# Cross.net
KiCad netlist of a schematic drawn in Altium Designer
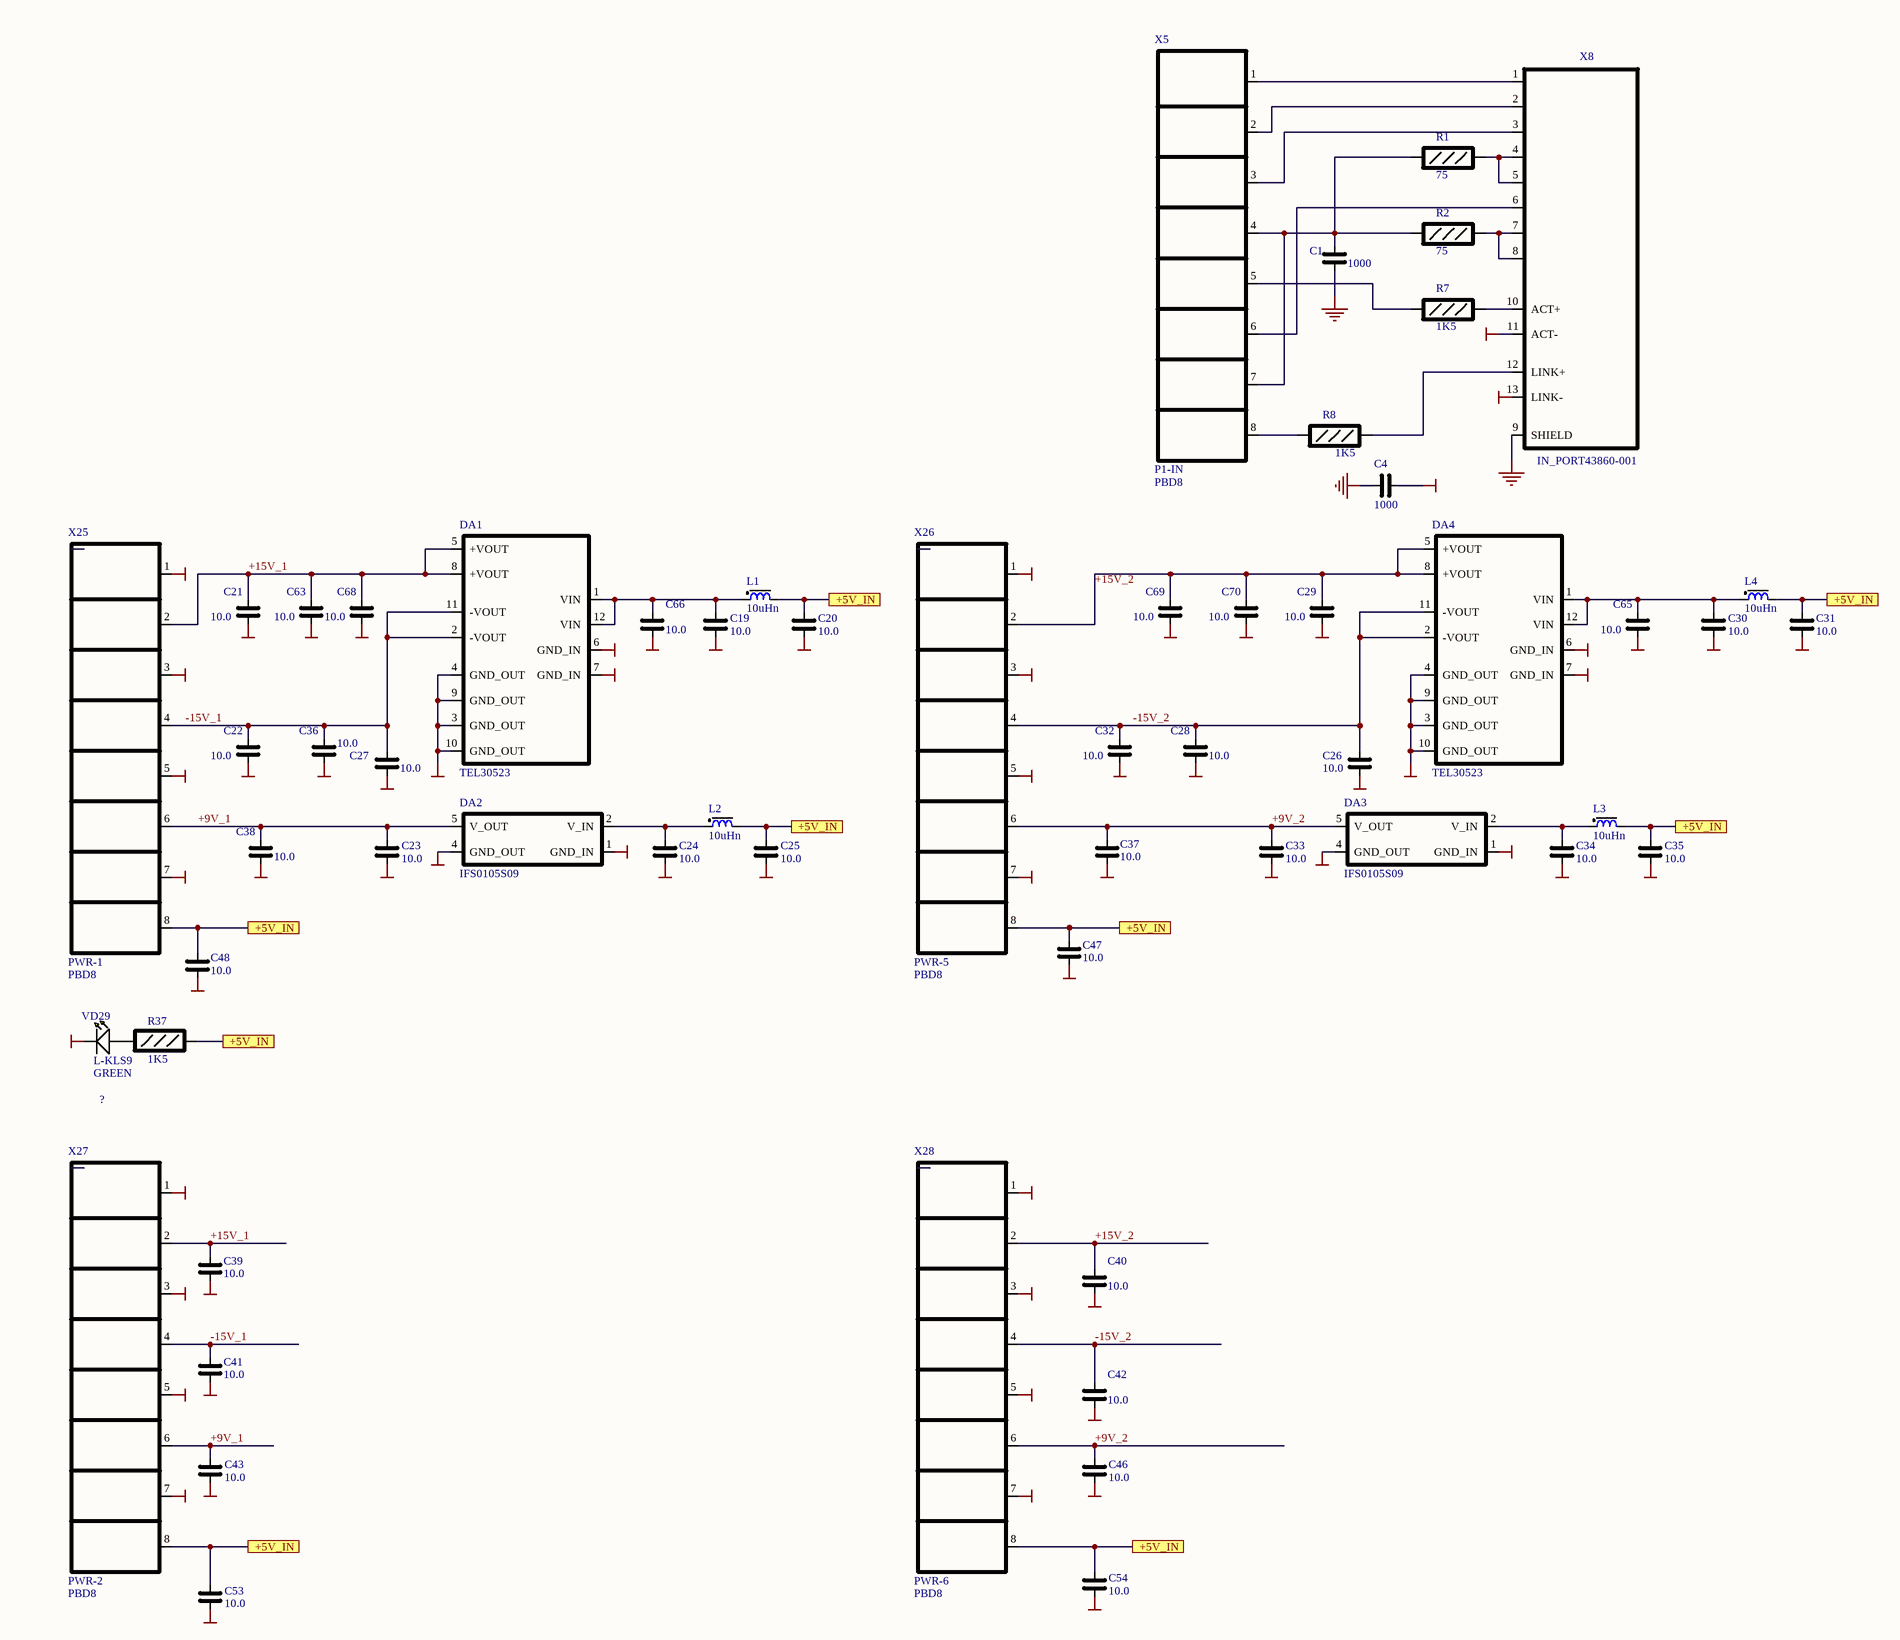
[diagram p0: Cross.SchDoc, top left]
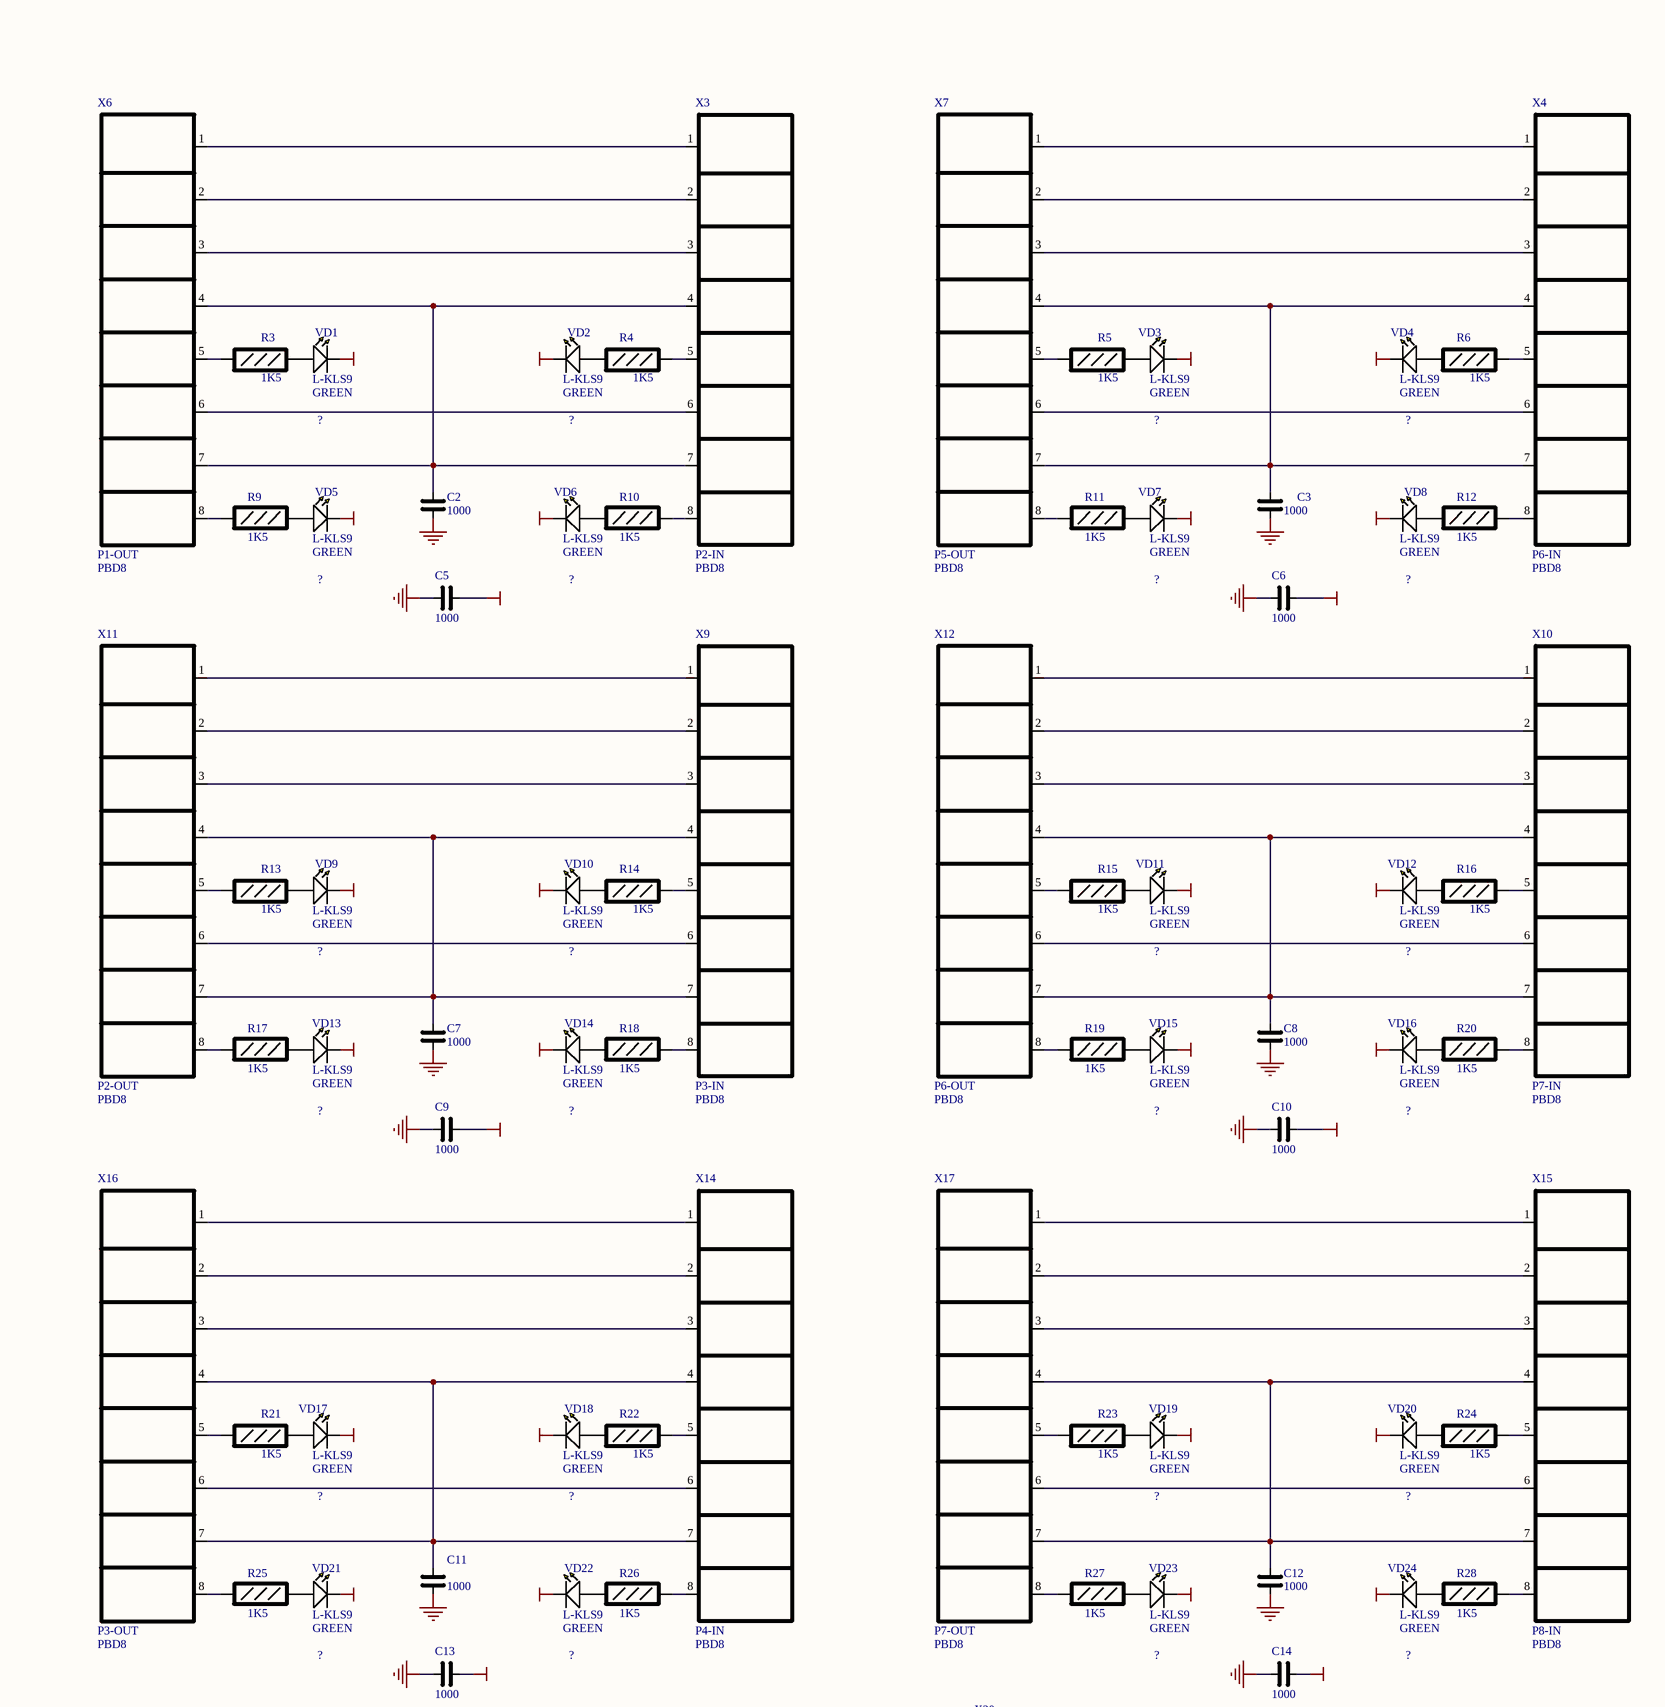
[diagram p1: Cross.SchDoc, top right]
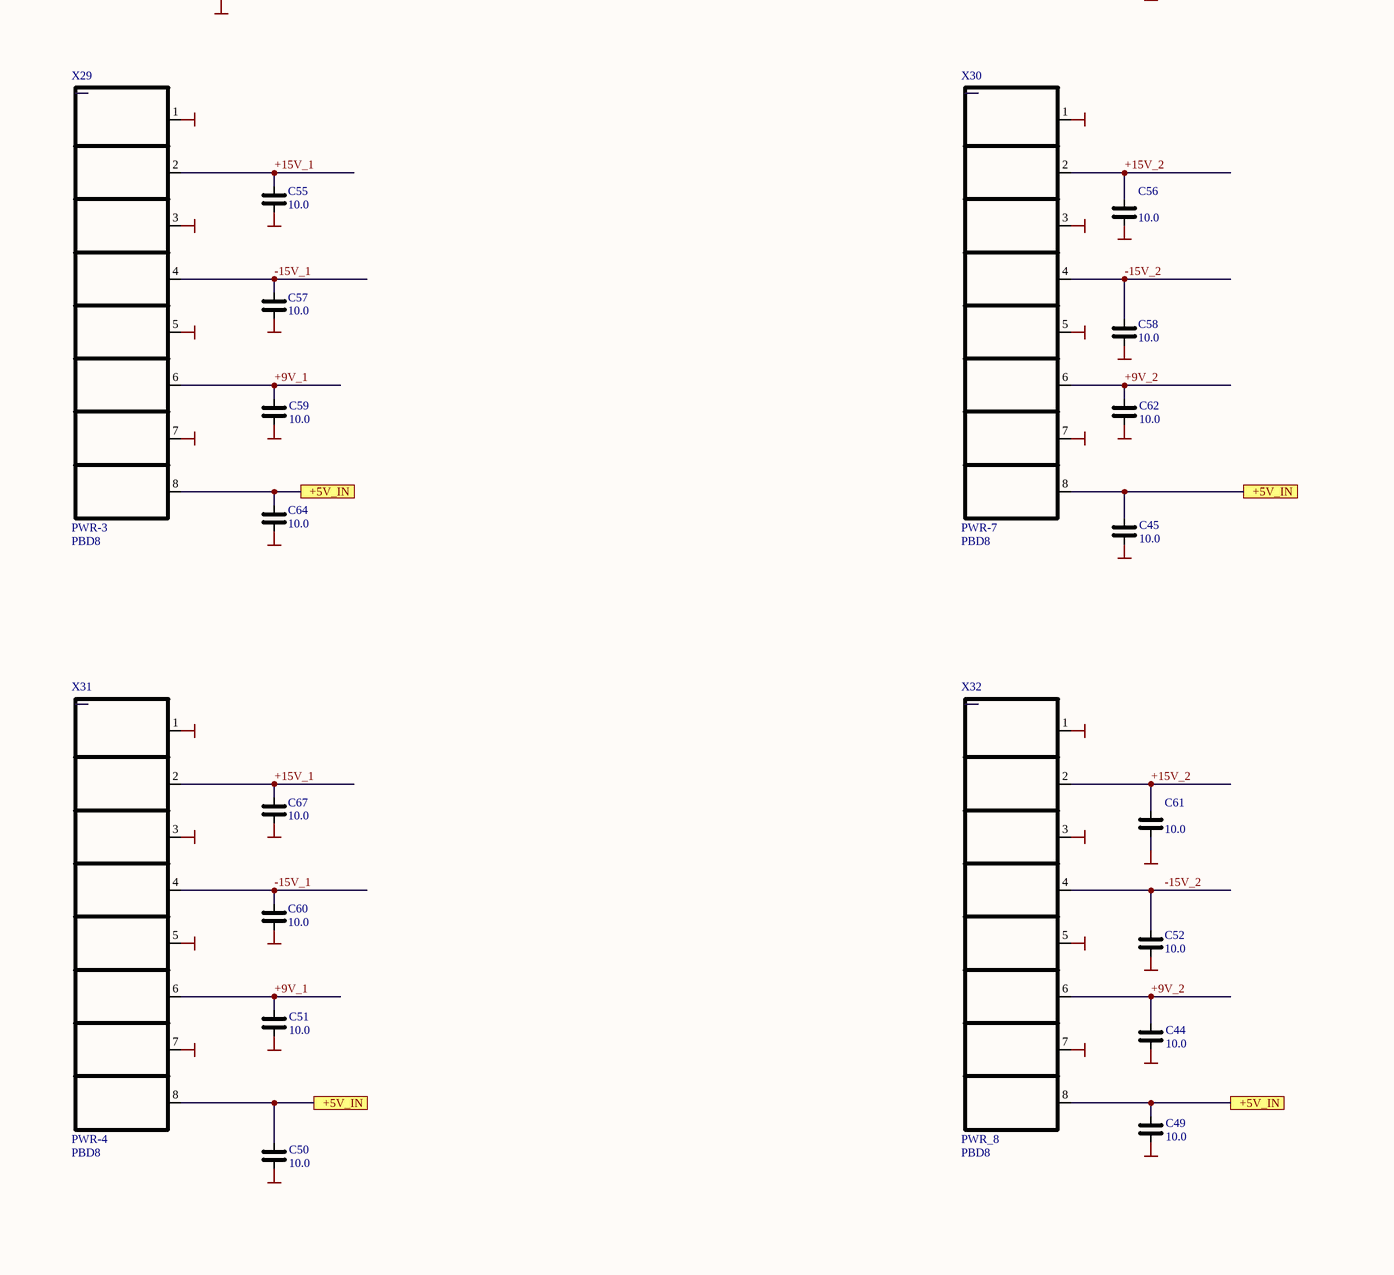
[diagram p2: Cross.SchDoc, bottom left]
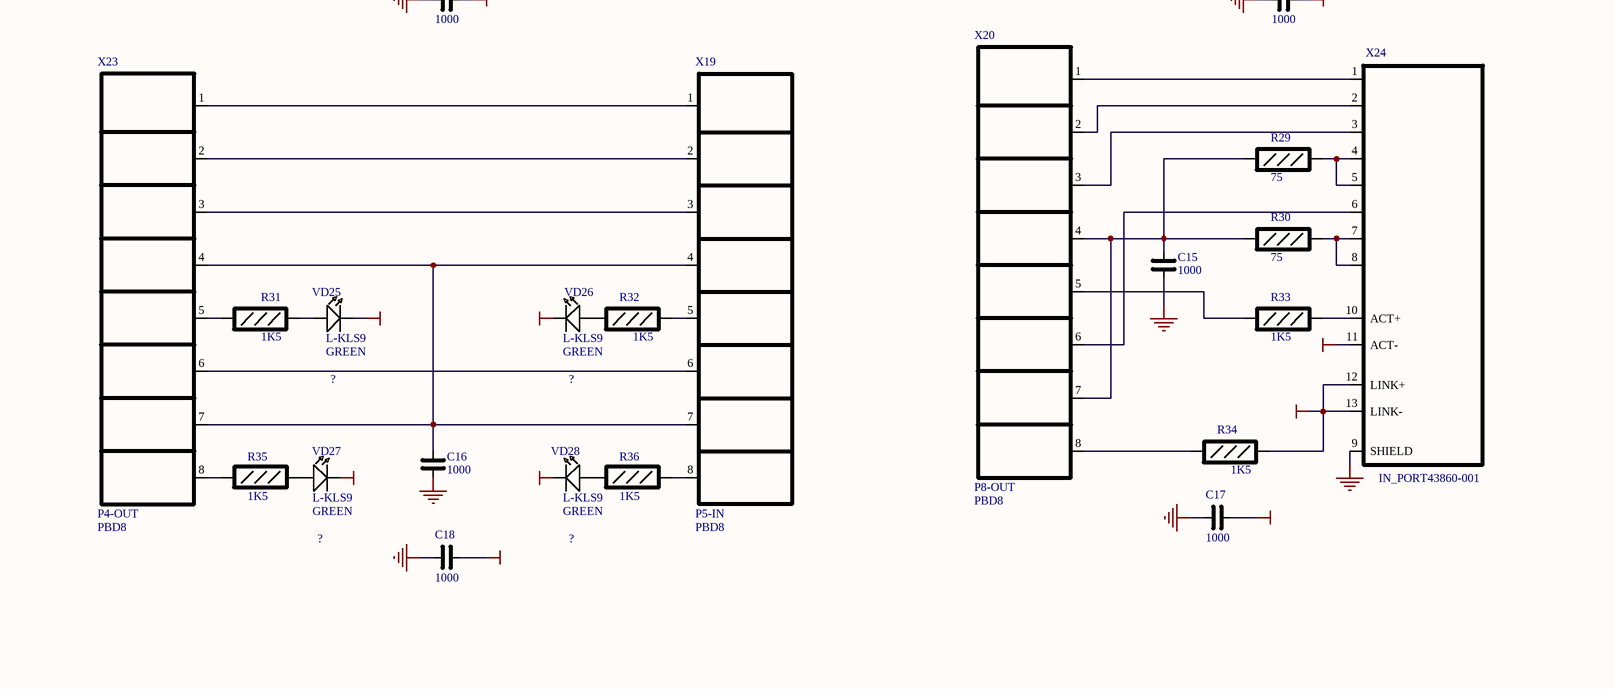
[diagram p3: Cross.SchDoc, bottom right]

(export (version "E")
  (design (tool "Eeschema 10.0.6"))
  (components
    (comp (ref "C1")
      (value "1000")
      (footprint "CAPC3225X168N")
      (description "Chip capasitor 1210")
      (libsource (lib "L1") (part "CAP1210"))
    )
    (comp (ref "C2")
      (value "1000")
      (footprint "CAPC3225X168N")
      (description "Chip capasitor 1210")
      (libsource (lib "L1") (part "CAP1210"))
    )
    (comp (ref "C3")
      (value "1000")
      (footprint "CAPC3225X168N")
      (description "Chip capasitor 1210")
      (libsource (lib "L1") (part "CAP1210"))
    )
    (comp (ref "C4")
      (value "1000")
      (footprint "CAPC3225X168N")
      (description "Chip capasitor 1210")
      (libsource (lib "L1") (part "CAP1210"))
    )
    (comp (ref "C5")
      (value "1000")
      (footprint "CAPC3225X168N")
      (description "Chip capasitor 1210")
      (libsource (lib "L1") (part "CAP1210"))
    )
    (comp (ref "C6")
      (value "1000")
      (footprint "CAPC3225X168N")
      (description "Chip capasitor 1210")
      (libsource (lib "L1") (part "CAP1210"))
    )
    (comp (ref "C7")
      (value "1000")
      (footprint "CAPC3225X168N")
      (description "Chip capasitor 1210")
      (libsource (lib "L1") (part "CAP1210"))
    )
    (comp (ref "C8")
      (value "1000")
      (footprint "CAPC3225X168N")
      (description "Chip capasitor 1210")
      (libsource (lib "L1") (part "CAP1210"))
    )
    (comp (ref "C9")
      (value "1000")
      (footprint "CAPC3225X168N")
      (description "Chip capasitor 1210")
      (libsource (lib "L1") (part "CAP1210"))
    )
    (comp (ref "C10")
      (value "1000")
      (footprint "CAPC3225X168N")
      (description "Chip capasitor 1210")
      (libsource (lib "L1") (part "CAP1210"))
    )
    (comp (ref "C11")
      (value "1000")
      (footprint "CAPC3225X168N")
      (description "Chip capasitor 1210")
      (libsource (lib "L1") (part "CAP1210"))
    )
    (comp (ref "C12")
      (value "1000")
      (footprint "CAPC3225X168N")
      (description "Chip capasitor 1210")
      (libsource (lib "L1") (part "CAP1210"))
    )
    (comp (ref "C13")
      (value "1000")
      (footprint "CAPC3225X168N")
      (description "Chip capasitor 1210")
      (libsource (lib "L1") (part "CAP1210"))
    )
    (comp (ref "C14")
      (value "1000")
      (footprint "CAPC3225X168N")
      (description "Chip capasitor 1210")
      (libsource (lib "L1") (part "CAP1210"))
    )
    (comp (ref "C15")
      (value "1000")
      (footprint "CAPC3225X168N")
      (description "Chip capasitor 1210")
      (libsource (lib "L1") (part "CAP1210"))
    )
    (comp (ref "C16")
      (value "1000")
      (footprint "CAPC3225X168N")
      (description "Chip capasitor 1210")
      (libsource (lib "L1") (part "CAP1210"))
    )
    (comp (ref "C17")
      (value "1000")
      (footprint "CAPC3225X168N")
      (description "Chip capasitor 1210")
      (libsource (lib "L1") (part "CAP1210"))
    )
    (comp (ref "C18")
      (value "1000")
      (footprint "CAPC3225X168N")
      (description "Chip capasitor 1210")
      (libsource (lib "L1") (part "CAP1210"))
    )
    (comp (ref "C19")
      (value "10.0")
      (footprint "CAPC2012X135N")
      (description "Chip capasitor 0805")
      (libsource (lib "L1") (part "CAP0805"))
    )
    (comp (ref "C20")
      (value "10.0")
      (footprint "CAPC2012X135N")
      (description "Chip capasitor 0805")
      (libsource (lib "L1") (part "CAP0805"))
    )
    (comp (ref "C21")
      (value "10.0")
      (footprint "CAPC2012X135N")
      (description "Chip capasitor 0805")
      (libsource (lib "L1") (part "CAP0805"))
    )
    (comp (ref "C22")
      (value "10.0")
      (footprint "CAPC2012X135N")
      (description "Chip capasitor 0805")
      (libsource (lib "L1") (part "CAP0805"))
    )
    (comp (ref "C23")
      (value "10.0")
      (footprint "CAPC2012X135N")
      (description "Chip capasitor 0805")
      (libsource (lib "L1") (part "CAP0805"))
    )
    (comp (ref "C24")
      (value "10.0")
      (footprint "CAPC2012X135N")
      (description "Chip capasitor 0805")
      (libsource (lib "L1") (part "CAP0805"))
    )
    (comp (ref "C25")
      (value "10.0")
      (footprint "CAPC2012X135N")
      (description "Chip capasitor 0805")
      (libsource (lib "L1") (part "CAP0805"))
    )
    (comp (ref "C26")
      (value "10.0")
      (footprint "CAPC2012X135N")
      (description "Chip capasitor 0805")
      (libsource (lib "L1") (part "CAP0805"))
    )
    (comp (ref "C27")
      (value "10.0")
      (footprint "CAPC2012X135N")
      (description "Chip capasitor 0805")
      (libsource (lib "L1") (part "CAP0805"))
    )
    (comp (ref "C28")
      (value "10.0")
      (footprint "CAPC2012X135N")
      (description "Chip capasitor 0805")
      (libsource (lib "L1") (part "CAP0805"))
    )
    (comp (ref "C29")
      (value "10.0")
      (footprint "CAPC2012X135N")
      (description "Chip capasitor 0805")
      (libsource (lib "L1") (part "CAP0805"))
    )
    (comp (ref "C30")
      (value "10.0")
      (footprint "CAPC2012X135N")
      (description "Chip capasitor 0805")
      (libsource (lib "L1") (part "CAP0805"))
    )
    (comp (ref "C31")
      (value "10.0")
      (footprint "CAPC2012X135N")
      (description "Chip capasitor 0805")
      (libsource (lib "L1") (part "CAP0805"))
    )
    (comp (ref "C32")
      (value "10.0")
      (footprint "CAPC2012X135N")
      (description "Chip capasitor 0805")
      (libsource (lib "L1") (part "CAP0805"))
    )
    (comp (ref "C33")
      (value "10.0")
      (footprint "CAPC2012X135N")
      (description "Chip capasitor 0805")
      (libsource (lib "L1") (part "CAP0805"))
    )
    (comp (ref "C34")
      (value "10.0")
      (footprint "CAPC2012X135N")
      (description "Chip capasitor 0805")
      (libsource (lib "L1") (part "CAP0805"))
    )
    (comp (ref "C35")
      (value "10.0")
      (footprint "CAPC2012X135N")
      (description "Chip capasitor 0805")
      (libsource (lib "L1") (part "CAP0805"))
    )
    (comp (ref "C36")
      (value "10.0")
      (footprint "CAPC2012X135N")
      (description "Chip capasitor 0805")
      (libsource (lib "L1") (part "CAP0805"))
    )
    (comp (ref "C37")
      (value "10.0")
      (footprint "CAPC2012X135N")
      (description "Chip capasitor 0805")
      (libsource (lib "L1") (part "CAP0805"))
    )
    (comp (ref "C38")
      (value "10.0")
      (footprint "CAPC2012X135N")
      (description "Chip capasitor 0805")
      (libsource (lib "L1") (part "CAP0805"))
    )
    (comp (ref "C39")
      (value "10.0")
      (footprint "CAPC2012X135N")
      (description "Chip capasitor 0805")
      (libsource (lib "L1") (part "CAP0805"))
    )
    (comp (ref "C40")
      (value "10.0")
      (footprint "CAPC2012X135N")
      (description "Chip capasitor 0805")
      (libsource (lib "L1") (part "CAP0805"))
    )
    (comp (ref "C41")
      (value "10.0")
      (footprint "CAPC2012X135N")
      (description "Chip capasitor 0805")
      (libsource (lib "L1") (part "CAP0805"))
    )
    (comp (ref "C42")
      (value "10.0")
      (footprint "CAPC2012X135N")
      (description "Chip capasitor 0805")
      (libsource (lib "L1") (part "CAP0805"))
    )
    (comp (ref "C43")
      (value "10.0")
      (footprint "CAPC2012X135N")
      (description "Chip capasitor 0805")
      (libsource (lib "L1") (part "CAP0805"))
    )
    (comp (ref "C44")
      (value "10.0")
      (footprint "CAPC2012X135N")
      (description "Chip capasitor 0805")
      (libsource (lib "L1") (part "CAP0805"))
    )
    (comp (ref "C45")
      (value "10.0")
      (footprint "CAPC2012X135N")
      (description "Chip capasitor 0805")
      (libsource (lib "L1") (part "CAP0805"))
    )
    (comp (ref "C46")
      (value "10.0")
      (footprint "CAPC2012X135N")
      (description "Chip capasitor 0805")
      (libsource (lib "L1") (part "CAP0805"))
    )
    (comp (ref "C47")
      (value "10.0")
      (footprint "CAPC2012X135N")
      (description "Chip capasitor 0805")
      (libsource (lib "L1") (part "CAP0805"))
    )
    (comp (ref "C48")
      (value "10.0")
      (footprint "CAPC2012X135N")
      (description "Chip capasitor 0805")
      (libsource (lib "L1") (part "CAP0805"))
    )
    (comp (ref "C49")
      (value "10.0")
      (footprint "CAPC2012X135N")
      (description "Chip capasitor 0805")
      (libsource (lib "L1") (part "CAP0805"))
    )
    (comp (ref "C50")
      (value "10.0")
      (footprint "CAPC2012X135N")
      (description "Chip capasitor 0805")
      (libsource (lib "L1") (part "CAP0805"))
    )
    (comp (ref "C51")
      (value "10.0")
      (footprint "CAPC2012X135N")
      (description "Chip capasitor 0805")
      (libsource (lib "L1") (part "CAP0805"))
    )
    (comp (ref "C52")
      (value "10.0")
      (footprint "CAPC2012X135N")
      (description "Chip capasitor 0805")
      (libsource (lib "L1") (part "CAP0805"))
    )
    (comp (ref "C53")
      (value "10.0")
      (footprint "CAPC2012X135N")
      (description "Chip capasitor 0805")
      (libsource (lib "L1") (part "CAP0805"))
    )
    (comp (ref "C54")
      (value "10.0")
      (footprint "CAPC2012X135N")
      (description "Chip capasitor 0805")
      (libsource (lib "L1") (part "CAP0805"))
    )
    (comp (ref "C55")
      (value "10.0")
      (footprint "CAPC2012X135N")
      (description "Chip capasitor 0805")
      (libsource (lib "L1") (part "CAP0805"))
    )
    (comp (ref "C56")
      (value "10.0")
      (footprint "CAPC2012X135N")
      (description "Chip capasitor 0805")
      (libsource (lib "L1") (part "CAP0805"))
    )
    (comp (ref "C57")
      (value "10.0")
      (footprint "CAPC2012X135N")
      (description "Chip capasitor 0805")
      (libsource (lib "L1") (part "CAP0805"))
    )
    (comp (ref "C58")
      (value "10.0")
      (footprint "CAPC2012X135N")
      (description "Chip capasitor 0805")
      (libsource (lib "L1") (part "CAP0805"))
    )
    (comp (ref "C59")
      (value "10.0")
      (footprint "CAPC2012X135N")
      (description "Chip capasitor 0805")
      (libsource (lib "L1") (part "CAP0805"))
    )
    (comp (ref "C60")
      (value "10.0")
      (footprint "CAPC2012X135N")
      (description "Chip capasitor 0805")
      (libsource (lib "L1") (part "CAP0805"))
    )
    (comp (ref "C61")
      (value "10.0")
      (footprint "CAPC2012X135N")
      (description "Chip capasitor 0805")
      (libsource (lib "L1") (part "CAP0805"))
    )
    (comp (ref "C62")
      (value "10.0")
      (footprint "CAPC2012X135N")
      (description "Chip capasitor 0805")
      (libsource (lib "L1") (part "CAP0805"))
    )
    (comp (ref "C63")
      (value "10.0")
      (footprint "CAPC2012X135N")
      (description "Chip capasitor 0805")
      (libsource (lib "L1") (part "CAP0805"))
    )
    (comp (ref "C64")
      (value "10.0")
      (footprint "CAPC2012X135N")
      (description "Chip capasitor 0805")
      (libsource (lib "L1") (part "CAP0805"))
    )
    (comp (ref "C65")
      (value "10.0")
      (footprint "CAPC2012X135N")
      (description "Chip capasitor 0805")
      (libsource (lib "L1") (part "CAP0805"))
    )
    (comp (ref "C66")
      (value "10.0")
      (footprint "CAPC2012X135N")
      (description "Chip capasitor 0805")
      (libsource (lib "L1") (part "CAP0805"))
    )
    (comp (ref "C67")
      (value "10.0")
      (footprint "CAPC2012X135N")
      (description "Chip capasitor 0805")
      (libsource (lib "L1") (part "CAP0805"))
    )
    (comp (ref "C68")
      (value "10.0")
      (footprint "CAPC2012X135N")
      (description "Chip capasitor 0805")
      (libsource (lib "L1") (part "CAP0805"))
    )
    (comp (ref "C69")
      (value "10.0")
      (footprint "CAPC2012X135N")
      (description "Chip capasitor 0805")
      (libsource (lib "L1") (part "CAP0805"))
    )
    (comp (ref "C70")
      (value "10.0")
      (footprint "CAPC2012X135N")
      (description "Chip capasitor 0805")
      (libsource (lib "L1") (part "CAP0805"))
    )
    (comp (ref "DA1")
      (value "TEL30523")
      (footprint "DIP_12_254_Spec0")
      (description "DC/DC convertor Vin to Dual +&- V out")
      (libsource (lib "L1") (part "TEL3-"))
    )
    (comp (ref "DA2")
      (value "IFS0105S09")
      (footprint "SOIC_8-254")
      (description "DC/DC convertor Vin4.4..5V5 to Single V out")
      (libsource (lib "L1") (part "IFS01"))
    )
    (comp (ref "DA3")
      (value "IFS0105S09")
      (footprint "SOIC_8-254")
      (description "DC/DC convertor Vin4.4..5V5 to Single V out")
      (libsource (lib "L1") (part "IFS01"))
    )
    (comp (ref "DA4")
      (value "TEL30523")
      (footprint "DIP_12_254_Spec0")
      (description "DC/DC convertor Vin to Dual +&- V out")
      (libsource (lib "L1") (part "TEL3-"))
    )
    (comp (ref "L1")
      (value "10uHn")
      (footprint "SMD2220")
      (description "Chip capasitor 1210")
      (libsource (lib "L1") (part "LQN6C"))
    )
    (comp (ref "L2")
      (value "10uHn")
      (footprint "SMD2220")
      (description "Chip capasitor 1210")
      (libsource (lib "L1") (part "LQN6C"))
    )
    (comp (ref "L3")
      (value "10uHn")
      (footprint "SMD2220")
      (description "Chip capasitor 1210")
      (libsource (lib "L1") (part "LQN6C"))
    )
    (comp (ref "L4")
      (value "10uHn")
      (footprint "SMD2220")
      (description "Chip capasitor 1210")
      (libsource (lib "L1") (part "LQN6C"))
    )
    (comp (ref "R1")
      (value "75")
      (footprint "RESC1608X50N")
      (description "Chip resistor 0603")
      (libsource (lib "L1") (part "Res0603"))
    )
    (comp (ref "R2")
      (value "75")
      (footprint "RESC1608X50N")
      (description "Chip resistor 0603")
      (libsource (lib "L1") (part "Res0603"))
    )
    (comp (ref "R3")
      (value "1K5")
      (footprint "RESC1608X50N")
      (description "Chip resistor 0603")
      (libsource (lib "L1") (part "Res0603"))
    )
    (comp (ref "R4")
      (value "1K5")
      (footprint "RESC1608X50N")
      (description "Chip resistor 0603")
      (libsource (lib "L1") (part "Res0603"))
    )
    (comp (ref "R5")
      (value "1K5")
      (footprint "RESC1608X50N")
      (description "Chip resistor 0603")
      (libsource (lib "L1") (part "Res0603"))
    )
    (comp (ref "R6")
      (value "1K5")
      (footprint "RESC1608X50N")
      (description "Chip resistor 0603")
      (libsource (lib "L1") (part "Res0603"))
    )
    (comp (ref "R7")
      (value "1K5")
      (footprint "RESC1608X50N")
      (description "Chip resistor 0603")
      (libsource (lib "L1") (part "Res0603"))
    )
    (comp (ref "R8")
      (value "1K5")
      (footprint "RESC1608X50N")
      (description "Chip resistor 0603")
      (libsource (lib "L1") (part "Res0603"))
    )
    (comp (ref "R9")
      (value "1K5")
      (footprint "RESC1608X50N")
      (description "Chip resistor 0603")
      (libsource (lib "") (part "Res0603_1"))
    )
    (comp (ref "R10")
      (value "1K5")
      (footprint "RESC1608X50N")
      (description "Chip resistor 0603")
      (libsource (lib "") (part "Res0603_1"))
    )
    (comp (ref "R11")
      (value "1K5")
      (footprint "RESC1608X50N")
      (description "Chip resistor 0603")
      (libsource (lib "") (part "Res0603_1"))
    )
    (comp (ref "R12")
      (value "1K5")
      (footprint "RESC1608X50N")
      (description "Chip resistor 0603")
      (libsource (lib "") (part "Res0603_1"))
    )
    (comp (ref "R13")
      (value "1K5")
      (footprint "RESC1608X50N")
      (description "Chip resistor 0603")
      (libsource (lib "L1") (part "Res0603"))
    )
    (comp (ref "R14")
      (value "1K5")
      (footprint "RESC1608X50N")
      (description "Chip resistor 0603")
      (libsource (lib "L1") (part "Res0603"))
    )
    (comp (ref "R15")
      (value "1K5")
      (footprint "RESC1608X50N")
      (description "Chip resistor 0603")
      (libsource (lib "L1") (part "Res0603"))
    )
    (comp (ref "R16")
      (value "1K5")
      (footprint "RESC1608X50N")
      (description "Chip resistor 0603")
      (libsource (lib "L1") (part "Res0603"))
    )
    (comp (ref "R17")
      (value "1K5")
      (footprint "RESC1608X50N")
      (description "Chip resistor 0603")
      (libsource (lib "") (part "Res0603_1"))
    )
    (comp (ref "R18")
      (value "1K5")
      (footprint "RESC1608X50N")
      (description "Chip resistor 0603")
      (libsource (lib "") (part "Res0603_1"))
    )
    (comp (ref "R19")
      (value "1K5")
      (footprint "RESC1608X50N")
      (description "Chip resistor 0603")
      (libsource (lib "") (part "Res0603_1"))
    )
    (comp (ref "R20")
      (value "1K5")
      (footprint "RESC1608X50N")
      (description "Chip resistor 0603")
      (libsource (lib "") (part "Res0603_1"))
    )
    (comp (ref "R21")
      (value "1K5")
      (footprint "RESC1608X50N")
      (description "Chip resistor 0603")
      (libsource (lib "L1") (part "Res0603"))
    )
    (comp (ref "R22")
      (value "1K5")
      (footprint "RESC1608X50N")
      (description "Chip resistor 0603")
      (libsource (lib "L1") (part "Res0603"))
    )
    (comp (ref "R23")
      (value "1K5")
      (footprint "RESC1608X50N")
      (description "Chip resistor 0603")
      (libsource (lib "L1") (part "Res0603"))
    )
    (comp (ref "R24")
      (value "1K5")
      (footprint "RESC1608X50N")
      (description "Chip resistor 0603")
      (libsource (lib "L1") (part "Res0603"))
    )
    (comp (ref "R25")
      (value "1K5")
      (footprint "RESC1608X50N")
      (description "Chip resistor 0603")
      (libsource (lib "") (part "Res0603_1"))
    )
    (comp (ref "R26")
      (value "1K5")
      (footprint "RESC1608X50N")
      (description "Chip resistor 0603")
      (libsource (lib "") (part "Res0603_1"))
    )
    (comp (ref "R27")
      (value "1K5")
      (footprint "RESC1608X50N")
      (description "Chip resistor 0603")
      (libsource (lib "") (part "Res0603_1"))
    )
    (comp (ref "R28")
      (value "1K5")
      (footprint "RESC1608X50N")
      (description "Chip resistor 0603")
      (libsource (lib "") (part "Res0603_1"))
    )
    (comp (ref "R29")
      (value "75")
      (footprint "RESC1608X50N")
      (description "Chip resistor 0603")
      (libsource (lib "L1") (part "Res0603"))
    )
    (comp (ref "R30")
      (value "75")
      (footprint "RESC1608X50N")
      (description "Chip resistor 0603")
      (libsource (lib "L1") (part "Res0603"))
    )
    (comp (ref "R31")
      (value "1K5")
      (footprint "RESC1608X50N")
      (description "Chip resistor 0603")
      (libsource (lib "L1") (part "Res0603"))
    )
    (comp (ref "R32")
      (value "1K5")
      (footprint "RESC1608X50N")
      (description "Chip resistor 0603")
      (libsource (lib "L1") (part "Res0603"))
    )
    (comp (ref "R33")
      (value "1K5")
      (footprint "RESC1608X50N")
      (description "Chip resistor 0603")
      (libsource (lib "L1") (part "Res0603"))
    )
    (comp (ref "R34")
      (value "1K5")
      (footprint "RESC1608X50N")
      (description "Chip resistor 0603")
      (libsource (lib "L1") (part "Res0603"))
    )
    (comp (ref "R35")
      (value "1K5")
      (footprint "RESC1608X50N")
      (description "Chip resistor 0603")
      (libsource (lib "") (part "Res0603_1"))
    )
    (comp (ref "R36")
      (value "1K5")
      (footprint "RESC1608X50N")
      (description "Chip resistor 0603")
      (libsource (lib "") (part "Res0603_1"))
    )
    (comp (ref "R37")
      (value "1K5")
      (footprint "RESC1608X50N")
      (description "Chip resistor 0603")
      (libsource (lib "") (part "Res0603_1"))
    )
    (comp (ref "VD1")
      (value "?")
      (footprint "LED0603")
      (description "Chip LED SMD 0603")
      (fields (field (name "DEVICE") "L-KLS9") (field (name "COLOR") "GREEN"))
      (libsource (lib "L1") (part "L-KLS9-T0603"))
    )
    (comp (ref "VD2")
      (value "?")
      (footprint "LED0603")
      (description "Chip LED SMD 0603")
      (fields (field (name "DEVICE") "L-KLS9") (field (name "COLOR") "GREEN"))
      (libsource (lib "L1") (part "L-KLS9-T0603"))
    )
    (comp (ref "VD3")
      (value "?")
      (footprint "LED0603")
      (description "Chip LED SMD 0603")
      (fields (field (name "DEVICE") "L-KLS9") (field (name "COLOR") "GREEN"))
      (libsource (lib "L1") (part "L-KLS9-T0603"))
    )
    (comp (ref "VD4")
      (value "?")
      (footprint "LED0603")
      (description "Chip LED SMD 0603")
      (fields (field (name "DEVICE") "L-KLS9") (field (name "COLOR") "GREEN"))
      (libsource (lib "L1") (part "L-KLS9-T0603"))
    )
    (comp (ref "VD5")
      (value "?")
      (footprint "LED0603")
      (description "Chip LED SMD 0603")
      (fields (field (name "DEVICE") "L-KLS9") (field (name "COLOR") "GREEN"))
      (libsource (lib "L1") (part "L-KLS9-T0603"))
    )
    (comp (ref "VD6")
      (value "?")
      (footprint "LED0603")
      (description "Chip LED SMD 0603")
      (fields (field (name "DEVICE") "L-KLS9") (field (name "COLOR") "GREEN"))
      (libsource (lib "L1") (part "L-KLS9-T0603"))
    )
    (comp (ref "VD7")
      (value "?")
      (footprint "LED0603")
      (description "Chip LED SMD 0603")
      (fields (field (name "DEVICE") "L-KLS9") (field (name "COLOR") "GREEN"))
      (libsource (lib "L1") (part "L-KLS9-T0603"))
    )
    (comp (ref "VD8")
      (value "?")
      (footprint "LED0603")
      (description "Chip LED SMD 0603")
      (fields (field (name "DEVICE") "L-KLS9") (field (name "COLOR") "GREEN"))
      (libsource (lib "L1") (part "L-KLS9-T0603"))
    )
    (comp (ref "VD9")
      (value "?")
      (footprint "LED0603")
      (description "Chip LED SMD 0603")
      (fields (field (name "DEVICE") "L-KLS9") (field (name "COLOR") "GREEN"))
      (libsource (lib "L1") (part "L-KLS9-T0603"))
    )
    (comp (ref "VD10")
      (value "?")
      (footprint "LED0603")
      (description "Chip LED SMD 0603")
      (fields (field (name "DEVICE") "L-KLS9") (field (name "COLOR") "GREEN"))
      (libsource (lib "L1") (part "L-KLS9-T0603"))
    )
    (comp (ref "VD11")
      (value "?")
      (footprint "LED0603")
      (description "Chip LED SMD 0603")
      (fields (field (name "DEVICE") "L-KLS9") (field (name "COLOR") "GREEN"))
      (libsource (lib "L1") (part "L-KLS9-T0603"))
    )
    (comp (ref "VD12")
      (value "?")
      (footprint "LED0603")
      (description "Chip LED SMD 0603")
      (fields (field (name "DEVICE") "L-KLS9") (field (name "COLOR") "GREEN"))
      (libsource (lib "L1") (part "L-KLS9-T0603"))
    )
    (comp (ref "VD13")
      (value "?")
      (footprint "LED0603")
      (description "Chip LED SMD 0603")
      (fields (field (name "DEVICE") "L-KLS9") (field (name "COLOR") "GREEN"))
      (libsource (lib "L1") (part "L-KLS9-T0603"))
    )
    (comp (ref "VD14")
      (value "?")
      (footprint "LED0603")
      (description "Chip LED SMD 0603")
      (fields (field (name "DEVICE") "L-KLS9") (field (name "COLOR") "GREEN"))
      (libsource (lib "L1") (part "L-KLS9-T0603"))
    )
    (comp (ref "VD15")
      (value "?")
      (footprint "LED0603")
      (description "Chip LED SMD 0603")
      (fields (field (name "DEVICE") "L-KLS9") (field (name "COLOR") "GREEN"))
      (libsource (lib "L1") (part "L-KLS9-T0603"))
    )
    (comp (ref "VD16")
      (value "?")
      (footprint "LED0603")
      (description "Chip LED SMD 0603")
      (fields (field (name "DEVICE") "L-KLS9") (field (name "COLOR") "GREEN"))
      (libsource (lib "L1") (part "L-KLS9-T0603"))
    )
    (comp (ref "VD17")
      (value "?")
      (footprint "LED0603")
      (description "Chip LED SMD 0603")
      (fields (field (name "DEVICE") "L-KLS9") (field (name "COLOR") "GREEN"))
      (libsource (lib "L1") (part "L-KLS9-T0603"))
    )
    (comp (ref "VD18")
      (value "?")
      (footprint "LED0603")
      (description "Chip LED SMD 0603")
      (fields (field (name "DEVICE") "L-KLS9") (field (name "COLOR") "GREEN"))
      (libsource (lib "L1") (part "L-KLS9-T0603"))
    )
    (comp (ref "VD19")
      (value "?")
      (footprint "LED0603")
      (description "Chip LED SMD 0603")
      (fields (field (name "DEVICE") "L-KLS9") (field (name "COLOR") "GREEN"))
      (libsource (lib "L1") (part "L-KLS9-T0603"))
    )
    (comp (ref "VD20")
      (value "?")
      (footprint "LED0603")
      (description "Chip LED SMD 0603")
      (fields (field (name "DEVICE") "L-KLS9") (field (name "COLOR") "GREEN"))
      (libsource (lib "L1") (part "L-KLS9-T0603"))
    )
    (comp (ref "VD21")
      (value "?")
      (footprint "LED0603")
      (description "Chip LED SMD 0603")
      (fields (field (name "DEVICE") "L-KLS9") (field (name "COLOR") "GREEN"))
      (libsource (lib "L1") (part "L-KLS9-T0603"))
    )
    (comp (ref "VD22")
      (value "?")
      (footprint "LED0603")
      (description "Chip LED SMD 0603")
      (fields (field (name "DEVICE") "L-KLS9") (field (name "COLOR") "GREEN"))
      (libsource (lib "L1") (part "L-KLS9-T0603"))
    )
    (comp (ref "VD23")
      (value "?")
      (footprint "LED0603")
      (description "Chip LED SMD 0603")
      (fields (field (name "DEVICE") "L-KLS9") (field (name "COLOR") "GREEN"))
      (libsource (lib "L1") (part "L-KLS9-T0603"))
    )
    (comp (ref "VD24")
      (value "?")
      (footprint "LED0603")
      (description "Chip LED SMD 0603")
      (fields (field (name "DEVICE") "L-KLS9") (field (name "COLOR") "GREEN"))
      (libsource (lib "L1") (part "L-KLS9-T0603"))
    )
    (comp (ref "VD25")
      (value "?")
      (footprint "LED0603")
      (description "Chip LED SMD 0603")
      (fields (field (name "DEVICE") "L-KLS9") (field (name "COLOR") "GREEN"))
      (libsource (lib "L1") (part "L-KLS9-T0603"))
    )
    (comp (ref "VD26")
      (value "?")
      (footprint "LED0603")
      (description "Chip LED SMD 0603")
      (fields (field (name "DEVICE") "L-KLS9") (field (name "COLOR") "GREEN"))
      (libsource (lib "L1") (part "L-KLS9-T0603"))
    )
    (comp (ref "VD27")
      (value "?")
      (footprint "LED0603")
      (description "Chip LED SMD 0603")
      (fields (field (name "DEVICE") "L-KLS9") (field (name "COLOR") "GREEN"))
      (libsource (lib "L1") (part "L-KLS9-T0603"))
    )
    (comp (ref "VD28")
      (value "?")
      (footprint "LED0603")
      (description "Chip LED SMD 0603")
      (fields (field (name "DEVICE") "L-KLS9") (field (name "COLOR") "GREEN"))
      (libsource (lib "L1") (part "L-KLS9-T0603"))
    )
    (comp (ref "VD29")
      (value "?")
      (footprint "LED0603")
      (description "Chip LED SMD 0603")
      (fields (field (name "DEVICE") "L-KLS9") (field (name "COLOR") "GREEN"))
      (libsource (lib "L1") (part "L-KLS9-T0603"))
    )
    (comp (ref "X3")
      (value "P2-IN")
      (footprint "DIP_8-254_F")
      (description "8 pin TRH socket 2.54mm pitch")
      (fields (field (name "DEVICE") "PBD8"))
      (libsource (lib "L1") (part "PBD8"))
    )
    (comp (ref "X4")
      (value "P6-IN")
      (footprint "DIP_8-254_F")
      (description "8 pin TRH socket 2.54mm pitch")
      (fields (field (name "DEVICE") "PBD8"))
      (libsource (lib "L1") (part "PBD8"))
    )
    (comp (ref "X5")
      (value "P1-IN")
      (footprint "DIP_8-254_F")
      (description "8 pin TRH socket 2.54mm pitch")
      (fields (field (name "DEVICE") "PBD8"))
      (libsource (lib "L1") (part "PBD8"))
    )
    (comp (ref "X6")
      (value "P1-OUT")
      (footprint "DIP_8-254_F")
      (description "8 pin TRH socket 2.54mm pitch")
      (fields (field (name "DEVICE") "PBD8"))
      (libsource (lib "L1") (part "PBD8"))
    )
    (comp (ref "X7")
      (value "P5-OUT")
      (footprint "DIP_8-254_F")
      (description "8 pin TRH socket 2.54mm pitch")
      (fields (field (name "DEVICE") "PBD8"))
      (libsource (lib "L1") (part "PBD8"))
    )
    (comp (ref "X8")
      (value "IN_PORT43860-001")
      (footprint "43860-0010")
      (description "RG45 THD Ethernet socket")
      (libsource (lib "L1") (part "RG45-43860-0010"))
    )
    (comp (ref "X9")
      (value "P3-IN")
      (footprint "DIP_8-254_F")
      (description "8 pin TRH socket 2.54mm pitch")
      (fields (field (name "DEVICE") "PBD8"))
      (libsource (lib "L1") (part "PBD8"))
    )
    (comp (ref "X10")
      (value "P7-IN")
      (footprint "DIP_8-254_F")
      (description "8 pin TRH socket 2.54mm pitch")
      (fields (field (name "DEVICE") "PBD8"))
      (libsource (lib "L1") (part "PBD8"))
    )
    (comp (ref "X11")
      (value "P2-OUT")
      (footprint "DIP_8-254_F")
      (description "8 pin TRH socket 2.54mm pitch")
      (fields (field (name "DEVICE") "PBD8"))
      (libsource (lib "L1") (part "PBD8"))
    )
    (comp (ref "X12")
      (value "P6-OUT")
      (footprint "DIP_8-254_F")
      (description "8 pin TRH socket 2.54mm pitch")
      (fields (field (name "DEVICE") "PBD8"))
      (libsource (lib "L1") (part "PBD8"))
    )
    (comp (ref "X14")
      (value "P4-IN")
      (footprint "DIP_8-254_F")
      (description "8 pin TRH socket 2.54mm pitch")
      (fields (field (name "DEVICE") "PBD8"))
      (libsource (lib "L1") (part "PBD8"))
    )
    (comp (ref "X15")
      (value "P8-IN")
      (footprint "DIP_8-254_F")
      (description "8 pin TRH socket 2.54mm pitch")
      (fields (field (name "DEVICE") "PBD8"))
      (libsource (lib "L1") (part "PBD8"))
    )
    (comp (ref "X16")
      (value "P3-OUT")
      (footprint "DIP_8-254_F")
      (description "8 pin TRH socket 2.54mm pitch")
      (fields (field (name "DEVICE") "PBD8"))
      (libsource (lib "L1") (part "PBD8"))
    )
    (comp (ref "X17")
      (value "P7-OUT")
      (footprint "DIP_8-254_F")
      (description "8 pin TRH socket 2.54mm pitch")
      (fields (field (name "DEVICE") "PBD8"))
      (libsource (lib "L1") (part "PBD8"))
    )
    (comp (ref "X19")
      (value "P5-IN")
      (footprint "DIP_8-254_F")
      (description "8 pin TRH socket 2.54mm pitch")
      (fields (field (name "DEVICE") "PBD8"))
      (libsource (lib "L1") (part "PBD8"))
    )
    (comp (ref "X20")
      (value "P8-OUT")
      (footprint "DIP_8-254_F")
      (description "8 pin TRH socket 2.54mm pitch")
      (fields (field (name "DEVICE") "PBD8"))
      (libsource (lib "L1") (part "PBD8"))
    )
    (comp (ref "X23")
      (value "P4-OUT")
      (footprint "DIP_8-254_F")
      (description "8 pin TRH socket 2.54mm pitch")
      (fields (field (name "DEVICE") "PBD8"))
      (libsource (lib "L1") (part "PBD8"))
    )
    (comp (ref "X24")
      (value "IN_PORT43860-001")
      (footprint "43860-0010")
      (description "RG45 THD Ethernet socket")
      (libsource (lib "L1") (part "RG45-43860-0010"))
    )
    (comp (ref "X25")
      (value "PWR-1")
      (footprint "DIP_8-254_F")
      (description "8 pin TRH socket 2.54mm pitch")
      (fields (field (name "DEVICE") "PBD8"))
      (libsource (lib "L1") (part "PBD8"))
    )
    (comp (ref "X26")
      (value "PWR-5")
      (footprint "DIP_8-254_F")
      (description "8 pin TRH socket 2.54mm pitch")
      (fields (field (name "DEVICE") "PBD8"))
      (libsource (lib "L1") (part "PBD8"))
    )
    (comp (ref "X27")
      (value "PWR-2")
      (footprint "DIP_8-254_F")
      (description "8 pin TRH socket 2.54mm pitch")
      (fields (field (name "DEVICE") "PBD8"))
      (libsource (lib "L1") (part "PBD8"))
    )
    (comp (ref "X28")
      (value "PWR-6")
      (footprint "DIP_8-254_F")
      (description "8 pin TRH socket 2.54mm pitch")
      (fields (field (name "DEVICE") "PBD8"))
      (libsource (lib "L1") (part "PBD8"))
    )
    (comp (ref "X29")
      (value "PWR-3")
      (footprint "DIP_8-254_F")
      (description "8 pin TRH socket 2.54mm pitch")
      (fields (field (name "DEVICE") "PBD8"))
      (libsource (lib "L1") (part "PBD8"))
    )
    (comp (ref "X30")
      (value "PWR-7")
      (footprint "DIP_8-254_F")
      (description "8 pin TRH socket 2.54mm pitch")
      (fields (field (name "DEVICE") "PBD8"))
      (libsource (lib "L1") (part "PBD8"))
    )
    (comp (ref "X31")
      (value "PWR-4")
      (footprint "DIP_8-254_F")
      (description "8 pin TRH socket 2.54mm pitch")
      (fields (field (name "DEVICE") "PBD8"))
      (libsource (lib "L1") (part "PBD8"))
    )
    (comp (ref "X32")
      (value "PWR_8")
      (footprint "DIP_8-254_F")
      (description "8 pin TRH socket 2.54mm pitch")
      (fields (field (name "DEVICE") "PBD8"))
      (libsource (lib "L1") (part "PBD8"))
    )
  )
  (nets
    (net (code "1") (name "/+5V_IN") (class "Default")
      (node (ref "C20") (pin "2") (pinfunction "2_2") (pintype "passive"))
      (node (ref "C25") (pin "2") (pinfunction "2_2") (pintype "passive"))
      (node (ref "C31") (pin "2") (pinfunction "2_2") (pintype "passive"))
      (node (ref "C35") (pin "2") (pinfunction "2_2") (pintype "passive"))
      (node (ref "C45") (pin "2") (pinfunction "2_2") (pintype "passive"))
      (node (ref "C47") (pin "2") (pinfunction "2_2") (pintype "passive"))
      (node (ref "C48") (pin "2") (pinfunction "2_2") (pintype "passive"))
      (node (ref "C49") (pin "2") (pinfunction "2_2") (pintype "passive"))
      (node (ref "C50") (pin "2") (pinfunction "2_2") (pintype "passive"))
      (node (ref "C53") (pin "2") (pinfunction "2_2") (pintype "passive"))
      (node (ref "C54") (pin "2") (pinfunction "2_2") (pintype "passive"))
      (node (ref "C64") (pin "2") (pinfunction "2_2") (pintype "passive"))
      (node (ref "L1") (pin "2") (pinfunction "2_2") (pintype "passive"))
      (node (ref "L2") (pin "2") (pinfunction "2_2") (pintype "passive"))
      (node (ref "L3") (pin "2") (pinfunction "2_2") (pintype "passive"))
      (node (ref "L4") (pin "2") (pinfunction "2_2") (pintype "passive"))
      (node (ref "R37") (pin "1") (pinfunction "1_1") (pintype "passive"))
      (node (ref "X25") (pin "8") (pinfunction "8_8") (pintype "passive"))
      (node (ref "X26") (pin "8") (pinfunction "8_8") (pintype "passive"))
      (node (ref "X27") (pin "8") (pinfunction "8_8") (pintype "passive"))
      (node (ref "X28") (pin "8") (pinfunction "8_8") (pintype "passive"))
      (node (ref "X29") (pin "8") (pinfunction "8_8") (pintype "passive"))
      (node (ref "X30") (pin "8") (pinfunction "8_8") (pintype "passive"))
      (node (ref "X31") (pin "8") (pinfunction "8_8") (pintype "passive"))
      (node (ref "X32") (pin "8") (pinfunction "8_8") (pintype "passive"))
    )
    (net (code "2") (name "/+9V_1") (class "Default")
      (node (ref "C23") (pin "2") (pinfunction "2_2") (pintype "passive"))
      (node (ref "C38") (pin "2") (pinfunction "2_2") (pintype "passive"))
      (node (ref "C43") (pin "2") (pinfunction "2_2") (pintype "passive"))
      (node (ref "C51") (pin "2") (pinfunction "2_2") (pintype "passive"))
      (node (ref "C59") (pin "2") (pinfunction "2_2") (pintype "passive"))
      (node (ref "DA2") (pin "5") (pinfunction "V_OUT_5") (pintype "power_in"))
      (node (ref "X25") (pin "6") (pinfunction "6_6") (pintype "passive"))
      (node (ref "X27") (pin "6") (pinfunction "6_6") (pintype "passive"))
      (node (ref "X29") (pin "6") (pinfunction "6_6") (pintype "passive"))
      (node (ref "X31") (pin "6") (pinfunction "6_6") (pintype "passive"))
    )
    (net (code "3") (name "/+9V_2") (class "Default")
      (node (ref "C33") (pin "2") (pinfunction "2_2") (pintype "passive"))
      (node (ref "C37") (pin "2") (pinfunction "2_2") (pintype "passive"))
      (node (ref "C44") (pin "2") (pinfunction "2_2") (pintype "passive"))
      (node (ref "C46") (pin "2") (pinfunction "2_2") (pintype "passive"))
      (node (ref "C62") (pin "2") (pinfunction "2_2") (pintype "passive"))
      (node (ref "DA3") (pin "5") (pinfunction "V_OUT_5") (pintype "power_in"))
      (node (ref "X26") (pin "6") (pinfunction "6_6") (pintype "passive"))
      (node (ref "X28") (pin "6") (pinfunction "6_6") (pintype "passive"))
      (node (ref "X30") (pin "6") (pinfunction "6_6") (pintype "passive"))
      (node (ref "X32") (pin "6") (pinfunction "6_6") (pintype "passive"))
    )
    (net (code "4") (name "/+15V_1") (class "Default")
      (node (ref "C21") (pin "2") (pinfunction "2_2") (pintype "passive"))
      (node (ref "C39") (pin "2") (pinfunction "2_2") (pintype "passive"))
      (node (ref "C55") (pin "2") (pinfunction "2_2") (pintype "passive"))
      (node (ref "C63") (pin "2") (pinfunction "2_2") (pintype "passive"))
      (node (ref "C67") (pin "2") (pinfunction "2_2") (pintype "passive"))
      (node (ref "C68") (pin "2") (pinfunction "2_2") (pintype "passive"))
      (node (ref "DA1") (pin "5") (pinfunction "+VOUT_5") (pintype "power_in"))
      (node (ref "DA1") (pin "8") (pinfunction "+VOUT_8") (pintype "power_in"))
      (node (ref "X25") (pin "2") (pinfunction "2_2") (pintype "passive"))
      (node (ref "X27") (pin "2") (pinfunction "2_2") (pintype "passive"))
      (node (ref "X29") (pin "2") (pinfunction "2_2") (pintype "passive"))
      (node (ref "X31") (pin "2") (pinfunction "2_2") (pintype "passive"))
    )
    (net (code "5") (name "/+15V_2") (class "Default")
      (node (ref "C29") (pin "2") (pinfunction "2_2") (pintype "passive"))
      (node (ref "C40") (pin "2") (pinfunction "2_2") (pintype "passive"))
      (node (ref "C56") (pin "2") (pinfunction "2_2") (pintype "passive"))
      (node (ref "C61") (pin "2") (pinfunction "2_2") (pintype "passive"))
      (node (ref "C69") (pin "2") (pinfunction "2_2") (pintype "passive"))
      (node (ref "C70") (pin "2") (pinfunction "2_2") (pintype "passive"))
      (node (ref "DA4") (pin "5") (pinfunction "+VOUT_5") (pintype "power_in"))
      (node (ref "DA4") (pin "8") (pinfunction "+VOUT_8") (pintype "power_in"))
      (node (ref "X26") (pin "2") (pinfunction "2_2") (pintype "passive"))
      (node (ref "X28") (pin "2") (pinfunction "2_2") (pintype "passive"))
      (node (ref "X30") (pin "2") (pinfunction "2_2") (pintype "passive"))
      (node (ref "X32") (pin "2") (pinfunction "2_2") (pintype "passive"))
    )
    (net (code "6") (name "/-15V_1") (class "Default")
      (node (ref "C22") (pin "2") (pinfunction "2_2") (pintype "passive"))
      (node (ref "C27") (pin "2") (pinfunction "2_2") (pintype "passive"))
      (node (ref "C36") (pin "2") (pinfunction "2_2") (pintype "passive"))
      (node (ref "C41") (pin "2") (pinfunction "2_2") (pintype "passive"))
      (node (ref "C57") (pin "2") (pinfunction "2_2") (pintype "passive"))
      (node (ref "C60") (pin "2") (pinfunction "2_2") (pintype "passive"))
      (node (ref "DA1") (pin "11") (pinfunction "-VOUT_11") (pintype "power_in"))
      (node (ref "DA1") (pin "2") (pinfunction "-VOUT_2") (pintype "power_in"))
      (node (ref "X25") (pin "4") (pinfunction "4_4") (pintype "passive"))
      (node (ref "X27") (pin "4") (pinfunction "4_4") (pintype "passive"))
      (node (ref "X29") (pin "4") (pinfunction "4_4") (pintype "passive"))
      (node (ref "X31") (pin "4") (pinfunction "4_4") (pintype "passive"))
    )
    (net (code "7") (name "/-15V_2") (class "Default")
      (node (ref "C26") (pin "2") (pinfunction "2_2") (pintype "passive"))
      (node (ref "C28") (pin "2") (pinfunction "2_2") (pintype "passive"))
      (node (ref "C32") (pin "2") (pinfunction "2_2") (pintype "passive"))
      (node (ref "C42") (pin "2") (pinfunction "2_2") (pintype "passive"))
      (node (ref "C52") (pin "2") (pinfunction "2_2") (pintype "passive"))
      (node (ref "C58") (pin "2") (pinfunction "2_2") (pintype "passive"))
      (node (ref "DA4") (pin "11") (pinfunction "-VOUT_11") (pintype "power_in"))
      (node (ref "DA4") (pin "2") (pinfunction "-VOUT_2") (pintype "power_in"))
      (node (ref "X26") (pin "4") (pinfunction "4_4") (pintype "passive"))
      (node (ref "X28") (pin "4") (pinfunction "4_4") (pintype "passive"))
      (node (ref "X30") (pin "4") (pinfunction "4_4") (pintype "passive"))
      (node (ref "X32") (pin "4") (pinfunction "4_4") (pintype "passive"))
    )
    (net (code "8") (name "GND") (class "Default")
      (node (ref "C10") (pin "2") (pinfunction "2_2") (pintype "passive"))
      (node (ref "C13") (pin "2") (pinfunction "2_2") (pintype "passive"))
      (node (ref "C14") (pin "2") (pinfunction "2_2") (pintype "passive"))
      (node (ref "C17") (pin "2") (pinfunction "2_2") (pintype "passive"))
      (node (ref "C18") (pin "2") (pinfunction "2_2") (pintype "passive"))
      (node (ref "C19") (pin "1") (pinfunction "1_1") (pintype "passive"))
      (node (ref "C20") (pin "1") (pinfunction "1_1") (pintype "passive"))
      (node (ref "C21") (pin "1") (pinfunction "1_1") (pintype "passive"))
      (node (ref "C22") (pin "1") (pinfunction "1_1") (pintype "passive"))
      (node (ref "C23") (pin "1") (pinfunction "1_1") (pintype "passive"))
      (node (ref "C24") (pin "1") (pinfunction "1_1") (pintype "passive"))
      (node (ref "C25") (pin "1") (pinfunction "1_1") (pintype "passive"))
      (node (ref "C26") (pin "1") (pinfunction "1_1") (pintype "passive"))
      (node (ref "C27") (pin "1") (pinfunction "1_1") (pintype "passive"))
      (node (ref "C28") (pin "1") (pinfunction "1_1") (pintype "passive"))
      (node (ref "C29") (pin "1") (pinfunction "1_1") (pintype "passive"))
      (node (ref "C30") (pin "1") (pinfunction "1_1") (pintype "passive"))
      (node (ref "C31") (pin "1") (pinfunction "1_1") (pintype "passive"))
      (node (ref "C32") (pin "1") (pinfunction "1_1") (pintype "passive"))
      (node (ref "C33") (pin "1") (pinfunction "1_1") (pintype "passive"))
      (node (ref "C34") (pin "1") (pinfunction "1_1") (pintype "passive"))
      (node (ref "C35") (pin "1") (pinfunction "1_1") (pintype "passive"))
      (node (ref "C36") (pin "1") (pinfunction "1_1") (pintype "passive"))
      (node (ref "C37") (pin "1") (pinfunction "1_1") (pintype "passive"))
      (node (ref "C38") (pin "1") (pinfunction "1_1") (pintype "passive"))
      (node (ref "C39") (pin "1") (pinfunction "1_1") (pintype "passive"))
      (node (ref "C4") (pin "2") (pinfunction "2_2") (pintype "passive"))
      (node (ref "C40") (pin "1") (pinfunction "1_1") (pintype "passive"))
      (node (ref "C41") (pin "1") (pinfunction "1_1") (pintype "passive"))
      (node (ref "C42") (pin "1") (pinfunction "1_1") (pintype "passive"))
      (node (ref "C43") (pin "1") (pinfunction "1_1") (pintype "passive"))
      (node (ref "C44") (pin "1") (pinfunction "1_1") (pintype "passive"))
      (node (ref "C45") (pin "1") (pinfunction "1_1") (pintype "passive"))
      (node (ref "C46") (pin "1") (pinfunction "1_1") (pintype "passive"))
      (node (ref "C47") (pin "1") (pinfunction "1_1") (pintype "passive"))
      (node (ref "C48") (pin "1") (pinfunction "1_1") (pintype "passive"))
      (node (ref "C49") (pin "1") (pinfunction "1_1") (pintype "passive"))
      (node (ref "C5") (pin "2") (pinfunction "2_2") (pintype "passive"))
      (node (ref "C50") (pin "1") (pinfunction "1_1") (pintype "passive"))
      (node (ref "C51") (pin "1") (pinfunction "1_1") (pintype "passive"))
      (node (ref "C52") (pin "1") (pinfunction "1_1") (pintype "passive"))
      (node (ref "C53") (pin "1") (pinfunction "1_1") (pintype "passive"))
      (node (ref "C54") (pin "1") (pinfunction "1_1") (pintype "passive"))
      (node (ref "C55") (pin "1") (pinfunction "1_1") (pintype "passive"))
      (node (ref "C56") (pin "1") (pinfunction "1_1") (pintype "passive"))
      (node (ref "C57") (pin "1") (pinfunction "1_1") (pintype "passive"))
      (node (ref "C58") (pin "1") (pinfunction "1_1") (pintype "passive"))
      (node (ref "C59") (pin "1") (pinfunction "1_1") (pintype "passive"))
      (node (ref "C6") (pin "2") (pinfunction "2_2") (pintype "passive"))
      (node (ref "C60") (pin "1") (pinfunction "1_1") (pintype "passive"))
      (node (ref "C61") (pin "1") (pinfunction "1_1") (pintype "passive"))
      (node (ref "C62") (pin "1") (pinfunction "1_1") (pintype "passive"))
      (node (ref "C63") (pin "1") (pinfunction "1_1") (pintype "passive"))
      (node (ref "C64") (pin "1") (pinfunction "1_1") (pintype "passive"))
      (node (ref "C65") (pin "1") (pinfunction "1_1") (pintype "passive"))
      (node (ref "C66") (pin "1") (pinfunction "1_1") (pintype "passive"))
      (node (ref "C67") (pin "1") (pinfunction "1_1") (pintype "passive"))
      (node (ref "C68") (pin "1") (pinfunction "1_1") (pintype "passive"))
      (node (ref "C69") (pin "1") (pinfunction "1_1") (pintype "passive"))
      (node (ref "C70") (pin "1") (pinfunction "1_1") (pintype "passive"))
      (node (ref "C9") (pin "2") (pinfunction "2_2") (pintype "passive"))
      (node (ref "DA1") (pin "10") (pinfunction "GND_OUT_10") (pintype "power_in"))
      (node (ref "DA1") (pin "3") (pinfunction "GND_OUT_3") (pintype "power_in"))
      (node (ref "DA1") (pin "4") (pinfunction "GND_OUT_4") (pintype "power_in"))
      (node (ref "DA1") (pin "6") (pinfunction "GND_IN_6") (pintype "power_in"))
      (node (ref "DA1") (pin "7") (pinfunction "GND_IN_7") (pintype "power_in"))
      (node (ref "DA1") (pin "9") (pinfunction "GND_OUT_9") (pintype "power_in"))
      (node (ref "DA2") (pin "1") (pinfunction "GND_IN_1") (pintype "power_in"))
      (node (ref "DA2") (pin "4") (pinfunction "GND_OUT_4") (pintype "power_in"))
      (node (ref "DA3") (pin "1") (pinfunction "GND_IN_1") (pintype "power_in"))
      (node (ref "DA3") (pin "4") (pinfunction "GND_OUT_4") (pintype "power_in"))
      (node (ref "DA4") (pin "10") (pinfunction "GND_OUT_10") (pintype "power_in"))
      (node (ref "DA4") (pin "3") (pinfunction "GND_OUT_3") (pintype "power_in"))
      (node (ref "DA4") (pin "4") (pinfunction "GND_OUT_4") (pintype "power_in"))
      (node (ref "DA4") (pin "6") (pinfunction "GND_IN_6") (pintype "power_in"))
      (node (ref "DA4") (pin "7") (pinfunction "GND_IN_7") (pintype "power_in"))
      (node (ref "DA4") (pin "9") (pinfunction "GND_OUT_9") (pintype "power_in"))
      (node (ref "R34") (pin "2") (pinfunction "2_2") (pintype "passive"))
      (node (ref "VD1") (pin "1") (pinfunction "C_1") (pintype "passive"))
      (node (ref "VD10") (pin "1") (pinfunction "C_1") (pintype "passive"))
      (node (ref "VD11") (pin "1") (pinfunction "C_1") (pintype "passive"))
      (node (ref "VD12") (pin "1") (pinfunction "C_1") (pintype "passive"))
      (node (ref "VD13") (pin "1") (pinfunction "C_1") (pintype "passive"))
      (node (ref "VD14") (pin "1") (pinfunction "C_1") (pintype "passive"))
      (node (ref "VD15") (pin "1") (pinfunction "C_1") (pintype "passive"))
      (node (ref "VD16") (pin "1") (pinfunction "C_1") (pintype "passive"))
      (node (ref "VD17") (pin "1") (pinfunction "C_1") (pintype "passive"))
      (node (ref "VD18") (pin "1") (pinfunction "C_1") (pintype "passive"))
      (node (ref "VD19") (pin "1") (pinfunction "C_1") (pintype "passive"))
      (node (ref "VD2") (pin "1") (pinfunction "C_1") (pintype "passive"))
      (node (ref "VD20") (pin "1") (pinfunction "C_1") (pintype "passive"))
      (node (ref "VD21") (pin "1") (pinfunction "C_1") (pintype "passive"))
      (node (ref "VD22") (pin "1") (pinfunction "C_1") (pintype "passive"))
      (node (ref "VD23") (pin "1") (pinfunction "C_1") (pintype "passive"))
      (node (ref "VD24") (pin "1") (pinfunction "C_1") (pintype "passive"))
      (node (ref "VD25") (pin "1") (pinfunction "C_1") (pintype "passive"))
      (node (ref "VD26") (pin "1") (pinfunction "C_1") (pintype "passive"))
      (node (ref "VD27") (pin "1") (pinfunction "C_1") (pintype "passive"))
      (node (ref "VD28") (pin "1") (pinfunction "C_1") (pintype "passive"))
      (node (ref "VD29") (pin "1") (pinfunction "C_1") (pintype "passive"))
      (node (ref "VD3") (pin "1") (pinfunction "C_1") (pintype "passive"))
      (node (ref "VD4") (pin "1") (pinfunction "C_1") (pintype "passive"))
      (node (ref "VD5") (pin "1") (pinfunction "C_1") (pintype "passive"))
      (node (ref "VD6") (pin "1") (pinfunction "C_1") (pintype "passive"))
      (node (ref "VD7") (pin "1") (pinfunction "C_1") (pintype "passive"))
      (node (ref "VD8") (pin "1") (pinfunction "C_1") (pintype "passive"))
      (node (ref "VD9") (pin "1") (pinfunction "C_1") (pintype "passive"))
      (node (ref "X24") (pin "11") (pinfunction "ACT-_11") (pintype "bidirectional"))
      (node (ref "X24") (pin "12") (pinfunction "LINK+_12") (pintype "bidirectional"))
      (node (ref "X24") (pin "13") (pinfunction "LINK-_13") (pintype "bidirectional"))
      (node (ref "X25") (pin "1") (pinfunction "1_1") (pintype "passive"))
      (node (ref "X25") (pin "3") (pinfunction "3_3") (pintype "passive"))
      (node (ref "X25") (pin "5") (pinfunction "5_5") (pintype "passive"))
      (node (ref "X25") (pin "7") (pinfunction "7_7") (pintype "passive"))
      (node (ref "X26") (pin "1") (pinfunction "1_1") (pintype "passive"))
      (node (ref "X26") (pin "3") (pinfunction "3_3") (pintype "passive"))
      (node (ref "X26") (pin "5") (pinfunction "5_5") (pintype "passive"))
      (node (ref "X26") (pin "7") (pinfunction "7_7") (pintype "passive"))
      (node (ref "X27") (pin "1") (pinfunction "1_1") (pintype "passive"))
      (node (ref "X27") (pin "3") (pinfunction "3_3") (pintype "passive"))
      (node (ref "X27") (pin "5") (pinfunction "5_5") (pintype "passive"))
      (node (ref "X27") (pin "7") (pinfunction "7_7") (pintype "passive"))
      (node (ref "X28") (pin "1") (pinfunction "1_1") (pintype "passive"))
      (node (ref "X28") (pin "3") (pinfunction "3_3") (pintype "passive"))
      (node (ref "X28") (pin "5") (pinfunction "5_5") (pintype "passive"))
      (node (ref "X28") (pin "7") (pinfunction "7_7") (pintype "passive"))
      (node (ref "X29") (pin "1") (pinfunction "1_1") (pintype "passive"))
      (node (ref "X29") (pin "3") (pinfunction "3_3") (pintype "passive"))
      (node (ref "X29") (pin "5") (pinfunction "5_5") (pintype "passive"))
      (node (ref "X29") (pin "7") (pinfunction "7_7") (pintype "passive"))
      (node (ref "X30") (pin "1") (pinfunction "1_1") (pintype "passive"))
      (node (ref "X30") (pin "3") (pinfunction "3_3") (pintype "passive"))
      (node (ref "X30") (pin "5") (pinfunction "5_5") (pintype "passive"))
      (node (ref "X30") (pin "7") (pinfunction "7_7") (pintype "passive"))
      (node (ref "X31") (pin "1") (pinfunction "1_1") (pintype "passive"))
      (node (ref "X31") (pin "3") (pinfunction "3_3") (pintype "passive"))
      (node (ref "X31") (pin "5") (pinfunction "5_5") (pintype "passive"))
      (node (ref "X31") (pin "7") (pinfunction "7_7") (pintype "passive"))
      (node (ref "X32") (pin "1") (pinfunction "1_1") (pintype "passive"))
      (node (ref "X32") (pin "3") (pinfunction "3_3") (pintype "passive"))
      (node (ref "X32") (pin "5") (pinfunction "5_5") (pintype "passive"))
      (node (ref "X32") (pin "7") (pinfunction "7_7") (pintype "passive"))
      (node (ref "X8") (pin "11") (pinfunction "ACT-_11") (pintype "bidirectional"))
      (node (ref "X8") (pin "13") (pinfunction "LINK-_13") (pintype "bidirectional"))
    )
    (net (code "9") (name "Net-(C1-Pad2)") (class "Default")
      (node (ref "C1") (pin "2") (pinfunction "2_2") (pintype "passive"))
      (node (ref "R1") (pin "1") (pinfunction "1_1") (pintype "passive"))
      (node (ref "R2") (pin "1") (pinfunction "1_1") (pintype "passive"))
      (node (ref "X5") (pin "4") (pinfunction "4_4") (pintype "passive"))
      (node (ref "X5") (pin "7") (pinfunction "7_7") (pintype "passive"))
    )
    (net (code "10") (name "Net-(C2-Pad2)") (class "Default")
      (node (ref "C2") (pin "2") (pinfunction "2_2") (pintype "passive"))
      (node (ref "X3") (pin "4") (pinfunction "4_4") (pintype "passive"))
      (node (ref "X3") (pin "7") (pinfunction "7_7") (pintype "passive"))
      (node (ref "X6") (pin "4") (pinfunction "4_4") (pintype "passive"))
      (node (ref "X6") (pin "7") (pinfunction "7_7") (pintype "passive"))
    )
    (net (code "11") (name "Net-(C3-Pad2)") (class "Default")
      (node (ref "C3") (pin "2") (pinfunction "2_2") (pintype "passive"))
      (node (ref "X4") (pin "4") (pinfunction "4_4") (pintype "passive"))
      (node (ref "X4") (pin "7") (pinfunction "7_7") (pintype "passive"))
      (node (ref "X7") (pin "4") (pinfunction "4_4") (pintype "passive"))
      (node (ref "X7") (pin "7") (pinfunction "7_7") (pintype "passive"))
    )
    (net (code "12") (name "Net-(C7-Pad2)") (class "Default")
      (node (ref "C7") (pin "2") (pinfunction "2_2") (pintype "passive"))
      (node (ref "X11") (pin "4") (pinfunction "4_4") (pintype "passive"))
      (node (ref "X11") (pin "7") (pinfunction "7_7") (pintype "passive"))
      (node (ref "X9") (pin "4") (pinfunction "4_4") (pintype "passive"))
      (node (ref "X9") (pin "7") (pinfunction "7_7") (pintype "passive"))
    )
    (net (code "13") (name "Net-(C8-Pad2)") (class "Default")
      (node (ref "C8") (pin "2") (pinfunction "2_2") (pintype "passive"))
      (node (ref "X10") (pin "4") (pinfunction "4_4") (pintype "passive"))
      (node (ref "X10") (pin "7") (pinfunction "7_7") (pintype "passive"))
      (node (ref "X12") (pin "4") (pinfunction "4_4") (pintype "passive"))
      (node (ref "X12") (pin "7") (pinfunction "7_7") (pintype "passive"))
    )
    (net (code "14") (name "Net-(C11-Pad2)") (class "Default")
      (node (ref "C11") (pin "2") (pinfunction "2_2") (pintype "passive"))
      (node (ref "X14") (pin "4") (pinfunction "4_4") (pintype "passive"))
      (node (ref "X14") (pin "7") (pinfunction "7_7") (pintype "passive"))
      (node (ref "X16") (pin "4") (pinfunction "4_4") (pintype "passive"))
      (node (ref "X16") (pin "7") (pinfunction "7_7") (pintype "passive"))
    )
    (net (code "15") (name "Net-(C12-Pad2)") (class "Default")
      (node (ref "C12") (pin "2") (pinfunction "2_2") (pintype "passive"))
      (node (ref "X15") (pin "4") (pinfunction "4_4") (pintype "passive"))
      (node (ref "X15") (pin "7") (pinfunction "7_7") (pintype "passive"))
      (node (ref "X17") (pin "4") (pinfunction "4_4") (pintype "passive"))
      (node (ref "X17") (pin "7") (pinfunction "7_7") (pintype "passive"))
    )
    (net (code "16") (name "Net-(C15-Pad2)") (class "Default")
      (node (ref "C15") (pin "2") (pinfunction "2_2") (pintype "passive"))
      (node (ref "R29") (pin "1") (pinfunction "1_1") (pintype "passive"))
      (node (ref "R30") (pin "1") (pinfunction "1_1") (pintype "passive"))
      (node (ref "X20") (pin "4") (pinfunction "4_4") (pintype "passive"))
      (node (ref "X20") (pin "7") (pinfunction "7_7") (pintype "passive"))
    )
    (net (code "17") (name "Net-(C16-Pad2)") (class "Default")
      (node (ref "C16") (pin "2") (pinfunction "2_2") (pintype "passive"))
      (node (ref "X19") (pin "4") (pinfunction "4_4") (pintype "passive"))
      (node (ref "X19") (pin "7") (pinfunction "7_7") (pintype "passive"))
      (node (ref "X23") (pin "4") (pinfunction "4_4") (pintype "passive"))
      (node (ref "X23") (pin "7") (pinfunction "7_7") (pintype "passive"))
    )
    (net (code "18") (name "Net-(C19-Pad2)") (class "Default")
      (node (ref "C19") (pin "2") (pinfunction "2_2") (pintype "passive"))
      (node (ref "C66") (pin "2") (pinfunction "2_2") (pintype "passive"))
      (node (ref "DA1") (pin "1") (pinfunction "VIN_1") (pintype "power_in"))
      (node (ref "DA1") (pin "12") (pinfunction "VIN_12") (pintype "power_in"))
      (node (ref "L1") (pin "1") (pinfunction "1_1") (pintype "passive"))
    )
    (net (code "19") (name "Net-(C30-Pad2)") (class "Default")
      (node (ref "C30") (pin "2") (pinfunction "2_2") (pintype "passive"))
      (node (ref "C65") (pin "2") (pinfunction "2_2") (pintype "passive"))
      (node (ref "DA4") (pin "1") (pinfunction "VIN_1") (pintype "power_in"))
      (node (ref "DA4") (pin "12") (pinfunction "VIN_12") (pintype "power_in"))
      (node (ref "L4") (pin "1") (pinfunction "1_1") (pintype "passive"))
    )
    (net (code "20") (name "Net-(DA2-V_IN)") (class "Default")
      (node (ref "C24") (pin "2") (pinfunction "2_2") (pintype "passive"))
      (node (ref "DA2") (pin "2") (pinfunction "V_IN_2") (pintype "power_in"))
      (node (ref "L2") (pin "1") (pinfunction "1_1") (pintype "passive"))
    )
    (net (code "21") (name "Net-(DA3-V_IN)") (class "Default")
      (node (ref "C34") (pin "2") (pinfunction "2_2") (pintype "passive"))
      (node (ref "DA3") (pin "2") (pinfunction "V_IN_2") (pintype "power_in"))
      (node (ref "L3") (pin "1") (pinfunction "1_1") (pintype "passive"))
    )
    (net (code "22") (name "Net-(R3-Pad1)") (class "Default")
      (node (ref "R3") (pin "1") (pinfunction "1_1") (pintype "passive"))
      (node (ref "X6") (pin "5") (pinfunction "5_5") (pintype "passive"))
    )
    (net (code "23") (name "Net-(R4-Pad2)") (class "Default")
      (node (ref "R4") (pin "2") (pinfunction "2_2") (pintype "passive"))
      (node (ref "X3") (pin "5") (pinfunction "5_5") (pintype "passive"))
    )
    (net (code "24") (name "Net-(R5-Pad1)") (class "Default")
      (node (ref "R5") (pin "1") (pinfunction "1_1") (pintype "passive"))
      (node (ref "X7") (pin "5") (pinfunction "5_5") (pintype "passive"))
    )
    (net (code "25") (name "Net-(R6-Pad2)") (class "Default")
      (node (ref "R6") (pin "2") (pinfunction "2_2") (pintype "passive"))
      (node (ref "X4") (pin "5") (pinfunction "5_5") (pintype "passive"))
    )
    (net (code "26") (name "Net-(R7-Pad1)") (class "Default")
      (node (ref "R7") (pin "1") (pinfunction "1_1") (pintype "passive"))
      (node (ref "X5") (pin "5") (pinfunction "5_5") (pintype "passive"))
    )
    (net (code "27") (name "Net-(R8-Pad1)") (class "Default")
      (node (ref "R8") (pin "1") (pinfunction "1_1") (pintype "passive"))
      (node (ref "X5") (pin "8") (pinfunction "8_8") (pintype "passive"))
    )
    (net (code "28") (name "Net-(R9-Pad2)") (class "Default")
      (node (ref "R9") (pin "2") (pinfunction "2_2") (pintype "passive"))
      (node (ref "X6") (pin "8") (pinfunction "8_8") (pintype "passive"))
    )
    (net (code "29") (name "Net-(R10-Pad1)") (class "Default")
      (node (ref "R10") (pin "1") (pinfunction "1_1") (pintype "passive"))
      (node (ref "X3") (pin "8") (pinfunction "8_8") (pintype "passive"))
    )
    (net (code "30") (name "Net-(R11-Pad2)") (class "Default")
      (node (ref "R11") (pin "2") (pinfunction "2_2") (pintype "passive"))
      (node (ref "X7") (pin "8") (pinfunction "8_8") (pintype "passive"))
    )
    (net (code "31") (name "Net-(R12-Pad1)") (class "Default")
      (node (ref "R12") (pin "1") (pinfunction "1_1") (pintype "passive"))
      (node (ref "X4") (pin "8") (pinfunction "8_8") (pintype "passive"))
    )
    (net (code "32") (name "Net-(R13-Pad1)") (class "Default")
      (node (ref "R13") (pin "1") (pinfunction "1_1") (pintype "passive"))
      (node (ref "X11") (pin "5") (pinfunction "5_5") (pintype "passive"))
    )
    (net (code "33") (name "Net-(R14-Pad2)") (class "Default")
      (node (ref "R14") (pin "2") (pinfunction "2_2") (pintype "passive"))
      (node (ref "X9") (pin "5") (pinfunction "5_5") (pintype "passive"))
    )
    (net (code "34") (name "Net-(R15-Pad1)") (class "Default")
      (node (ref "R15") (pin "1") (pinfunction "1_1") (pintype "passive"))
      (node (ref "X12") (pin "5") (pinfunction "5_5") (pintype "passive"))
    )
    (net (code "35") (name "Net-(R16-Pad2)") (class "Default")
      (node (ref "R16") (pin "2") (pinfunction "2_2") (pintype "passive"))
      (node (ref "X10") (pin "5") (pinfunction "5_5") (pintype "passive"))
    )
    (net (code "36") (name "Net-(R17-Pad2)") (class "Default")
      (node (ref "R17") (pin "2") (pinfunction "2_2") (pintype "passive"))
      (node (ref "X11") (pin "8") (pinfunction "8_8") (pintype "passive"))
    )
    (net (code "37") (name "Net-(R18-Pad1)") (class "Default")
      (node (ref "R18") (pin "1") (pinfunction "1_1") (pintype "passive"))
      (node (ref "X9") (pin "8") (pinfunction "8_8") (pintype "passive"))
    )
    (net (code "38") (name "Net-(R19-Pad2)") (class "Default")
      (node (ref "R19") (pin "2") (pinfunction "2_2") (pintype "passive"))
      (node (ref "X12") (pin "8") (pinfunction "8_8") (pintype "passive"))
    )
    (net (code "39") (name "Net-(R20-Pad1)") (class "Default")
      (node (ref "R20") (pin "1") (pinfunction "1_1") (pintype "passive"))
      (node (ref "X10") (pin "8") (pinfunction "8_8") (pintype "passive"))
    )
    (net (code "40") (name "Net-(R21-Pad1)") (class "Default")
      (node (ref "R21") (pin "1") (pinfunction "1_1") (pintype "passive"))
      (node (ref "X16") (pin "5") (pinfunction "5_5") (pintype "passive"))
    )
    (net (code "41") (name "Net-(R22-Pad2)") (class "Default")
      (node (ref "R22") (pin "2") (pinfunction "2_2") (pintype "passive"))
      (node (ref "X14") (pin "5") (pinfunction "5_5") (pintype "passive"))
    )
    (net (code "42") (name "Net-(R23-Pad1)") (class "Default")
      (node (ref "R23") (pin "1") (pinfunction "1_1") (pintype "passive"))
      (node (ref "X17") (pin "5") (pinfunction "5_5") (pintype "passive"))
    )
    (net (code "43") (name "Net-(R24-Pad2)") (class "Default")
      (node (ref "R24") (pin "2") (pinfunction "2_2") (pintype "passive"))
      (node (ref "X15") (pin "5") (pinfunction "5_5") (pintype "passive"))
    )
    (net (code "44") (name "Net-(R25-Pad2)") (class "Default")
      (node (ref "R25") (pin "2") (pinfunction "2_2") (pintype "passive"))
      (node (ref "X16") (pin "8") (pinfunction "8_8") (pintype "passive"))
    )
    (net (code "45") (name "Net-(R26-Pad1)") (class "Default")
      (node (ref "R26") (pin "1") (pinfunction "1_1") (pintype "passive"))
      (node (ref "X14") (pin "8") (pinfunction "8_8") (pintype "passive"))
    )
    (net (code "46") (name "Net-(R27-Pad2)") (class "Default")
      (node (ref "R27") (pin "2") (pinfunction "2_2") (pintype "passive"))
      (node (ref "X17") (pin "8") (pinfunction "8_8") (pintype "passive"))
    )
    (net (code "47") (name "Net-(R28-Pad1)") (class "Default")
      (node (ref "R28") (pin "1") (pinfunction "1_1") (pintype "passive"))
      (node (ref "X15") (pin "8") (pinfunction "8_8") (pintype "passive"))
    )
    (net (code "48") (name "Net-(R31-Pad1)") (class "Default")
      (node (ref "R31") (pin "1") (pinfunction "1_1") (pintype "passive"))
      (node (ref "X23") (pin "5") (pinfunction "5_5") (pintype "passive"))
    )
    (net (code "49") (name "Net-(R32-Pad2)") (class "Default")
      (node (ref "R32") (pin "2") (pinfunction "2_2") (pintype "passive"))
      (node (ref "X19") (pin "5") (pinfunction "5_5") (pintype "passive"))
    )
    (net (code "50") (name "Net-(R33-Pad1)") (class "Default")
      (node (ref "R33") (pin "1") (pinfunction "1_1") (pintype "passive"))
      (node (ref "X20") (pin "5") (pinfunction "5_5") (pintype "passive"))
    )
    (net (code "51") (name "Net-(R34-Pad1)") (class "Default")
      (node (ref "R34") (pin "1") (pinfunction "1_1") (pintype "passive"))
      (node (ref "X20") (pin "8") (pinfunction "8_8") (pintype "passive"))
    )
    (net (code "52") (name "Net-(R35-Pad2)") (class "Default")
      (node (ref "R35") (pin "2") (pinfunction "2_2") (pintype "passive"))
      (node (ref "X23") (pin "8") (pinfunction "8_8") (pintype "passive"))
    )
    (net (code "53") (name "Net-(R36-Pad1)") (class "Default")
      (node (ref "R36") (pin "1") (pinfunction "1_1") (pintype "passive"))
      (node (ref "X19") (pin "8") (pinfunction "8_8") (pintype "passive"))
    )
    (net (code "54") (name "Net-(VD1-A)") (class "Default")
      (node (ref "R3") (pin "2") (pinfunction "2_2") (pintype "passive"))
      (node (ref "VD1") (pin "2") (pinfunction "A_2") (pintype "passive"))
    )
    (net (code "55") (name "Net-(VD2-A)") (class "Default")
      (node (ref "R4") (pin "1") (pinfunction "1_1") (pintype "passive"))
      (node (ref "VD2") (pin "2") (pinfunction "A_2") (pintype "passive"))
    )
    (net (code "56") (name "Net-(VD3-A)") (class "Default")
      (node (ref "R5") (pin "2") (pinfunction "2_2") (pintype "passive"))
      (node (ref "VD3") (pin "2") (pinfunction "A_2") (pintype "passive"))
    )
    (net (code "57") (name "Net-(VD4-A)") (class "Default")
      (node (ref "R6") (pin "1") (pinfunction "1_1") (pintype "passive"))
      (node (ref "VD4") (pin "2") (pinfunction "A_2") (pintype "passive"))
    )
    (net (code "58") (name "Net-(VD5-A)") (class "Default")
      (node (ref "R9") (pin "1") (pinfunction "1_1") (pintype "passive"))
      (node (ref "VD5") (pin "2") (pinfunction "A_2") (pintype "passive"))
    )
    (net (code "59") (name "Net-(VD6-A)") (class "Default")
      (node (ref "R10") (pin "2") (pinfunction "2_2") (pintype "passive"))
      (node (ref "VD6") (pin "2") (pinfunction "A_2") (pintype "passive"))
    )
    (net (code "60") (name "Net-(VD7-A)") (class "Default")
      (node (ref "R11") (pin "1") (pinfunction "1_1") (pintype "passive"))
      (node (ref "VD7") (pin "2") (pinfunction "A_2") (pintype "passive"))
    )
    (net (code "61") (name "Net-(VD8-A)") (class "Default")
      (node (ref "R12") (pin "2") (pinfunction "2_2") (pintype "passive"))
      (node (ref "VD8") (pin "2") (pinfunction "A_2") (pintype "passive"))
    )
    (net (code "62") (name "Net-(VD9-A)") (class "Default")
      (node (ref "R13") (pin "2") (pinfunction "2_2") (pintype "passive"))
      (node (ref "VD9") (pin "2") (pinfunction "A_2") (pintype "passive"))
    )
    (net (code "63") (name "Net-(VD10-A)") (class "Default")
      (node (ref "R14") (pin "1") (pinfunction "1_1") (pintype "passive"))
      (node (ref "VD10") (pin "2") (pinfunction "A_2") (pintype "passive"))
    )
    (net (code "64") (name "Net-(VD11-A)") (class "Default")
      (node (ref "R15") (pin "2") (pinfunction "2_2") (pintype "passive"))
      (node (ref "VD11") (pin "2") (pinfunction "A_2") (pintype "passive"))
    )
    (net (code "65") (name "Net-(VD12-A)") (class "Default")
      (node (ref "R16") (pin "1") (pinfunction "1_1") (pintype "passive"))
      (node (ref "VD12") (pin "2") (pinfunction "A_2") (pintype "passive"))
    )
    (net (code "66") (name "Net-(VD13-A)") (class "Default")
      (node (ref "R17") (pin "1") (pinfunction "1_1") (pintype "passive"))
      (node (ref "VD13") (pin "2") (pinfunction "A_2") (pintype "passive"))
    )
    (net (code "67") (name "Net-(VD14-A)") (class "Default")
      (node (ref "R18") (pin "2") (pinfunction "2_2") (pintype "passive"))
      (node (ref "VD14") (pin "2") (pinfunction "A_2") (pintype "passive"))
    )
    (net (code "68") (name "Net-(VD15-A)") (class "Default")
      (node (ref "R19") (pin "1") (pinfunction "1_1") (pintype "passive"))
      (node (ref "VD15") (pin "2") (pinfunction "A_2") (pintype "passive"))
    )
    (net (code "69") (name "Net-(VD16-A)") (class "Default")
      (node (ref "R20") (pin "2") (pinfunction "2_2") (pintype "passive"))
      (node (ref "VD16") (pin "2") (pinfunction "A_2") (pintype "passive"))
    )
    (net (code "70") (name "Net-(VD17-A)") (class "Default")
      (node (ref "R21") (pin "2") (pinfunction "2_2") (pintype "passive"))
      (node (ref "VD17") (pin "2") (pinfunction "A_2") (pintype "passive"))
    )
    (net (code "71") (name "Net-(VD18-A)") (class "Default")
      (node (ref "R22") (pin "1") (pinfunction "1_1") (pintype "passive"))
      (node (ref "VD18") (pin "2") (pinfunction "A_2") (pintype "passive"))
    )
    (net (code "72") (name "Net-(VD19-A)") (class "Default")
      (node (ref "R23") (pin "2") (pinfunction "2_2") (pintype "passive"))
      (node (ref "VD19") (pin "2") (pinfunction "A_2") (pintype "passive"))
    )
    (net (code "73") (name "Net-(VD20-A)") (class "Default")
      (node (ref "R24") (pin "1") (pinfunction "1_1") (pintype "passive"))
      (node (ref "VD20") (pin "2") (pinfunction "A_2") (pintype "passive"))
    )
    (net (code "74") (name "Net-(VD21-A)") (class "Default")
      (node (ref "R25") (pin "1") (pinfunction "1_1") (pintype "passive"))
      (node (ref "VD21") (pin "2") (pinfunction "A_2") (pintype "passive"))
    )
    (net (code "75") (name "Net-(VD22-A)") (class "Default")
      (node (ref "R26") (pin "2") (pinfunction "2_2") (pintype "passive"))
      (node (ref "VD22") (pin "2") (pinfunction "A_2") (pintype "passive"))
    )
    (net (code "76") (name "Net-(VD23-A)") (class "Default")
      (node (ref "R27") (pin "1") (pinfunction "1_1") (pintype "passive"))
      (node (ref "VD23") (pin "2") (pinfunction "A_2") (pintype "passive"))
    )
    (net (code "77") (name "Net-(VD24-A)") (class "Default")
      (node (ref "R28") (pin "2") (pinfunction "2_2") (pintype "passive"))
      (node (ref "VD24") (pin "2") (pinfunction "A_2") (pintype "passive"))
    )
    (net (code "78") (name "Net-(VD25-A)") (class "Default")
      (node (ref "R31") (pin "2") (pinfunction "2_2") (pintype "passive"))
      (node (ref "VD25") (pin "2") (pinfunction "A_2") (pintype "passive"))
    )
    (net (code "79") (name "Net-(VD26-A)") (class "Default")
      (node (ref "R32") (pin "1") (pinfunction "1_1") (pintype "passive"))
      (node (ref "VD26") (pin "2") (pinfunction "A_2") (pintype "passive"))
    )
    (net (code "80") (name "Net-(VD27-A)") (class "Default")
      (node (ref "R35") (pin "1") (pinfunction "1_1") (pintype "passive"))
      (node (ref "VD27") (pin "2") (pinfunction "A_2") (pintype "passive"))
    )
    (net (code "81") (name "Net-(VD28-A)") (class "Default")
      (node (ref "R36") (pin "2") (pinfunction "2_2") (pintype "passive"))
      (node (ref "VD28") (pin "2") (pinfunction "A_2") (pintype "passive"))
    )
    (net (code "82") (name "Net-(VD29-A)") (class "Default")
      (node (ref "R37") (pin "2") (pinfunction "2_2") (pintype "passive"))
      (node (ref "VD29") (pin "2") (pinfunction "A_2") (pintype "passive"))
    )
    (net (code "83") (name "Net-(X3-Pad1)") (class "Default")
      (node (ref "X3") (pin "1") (pinfunction "1_1") (pintype "passive"))
      (node (ref "X6") (pin "1") (pinfunction "1_1") (pintype "passive"))
    )
    (net (code "84") (name "Net-(X3-Pad2)") (class "Default")
      (node (ref "X3") (pin "2") (pinfunction "2_2") (pintype "passive"))
      (node (ref "X6") (pin "2") (pinfunction "2_2") (pintype "passive"))
    )
    (net (code "85") (name "Net-(X3-Pad3)") (class "Default")
      (node (ref "X3") (pin "3") (pinfunction "3_3") (pintype "passive"))
      (node (ref "X6") (pin "3") (pinfunction "3_3") (pintype "passive"))
    )
    (net (code "86") (name "Net-(X3-Pad6)") (class "Default")
      (node (ref "X3") (pin "6") (pinfunction "6_6") (pintype "passive"))
      (node (ref "X6") (pin "6") (pinfunction "6_6") (pintype "passive"))
    )
    (net (code "87") (name "Net-(X4-Pad1)") (class "Default")
      (node (ref "X4") (pin "1") (pinfunction "1_1") (pintype "passive"))
      (node (ref "X7") (pin "1") (pinfunction "1_1") (pintype "passive"))
    )
    (net (code "88") (name "Net-(X4-Pad2)") (class "Default")
      (node (ref "X4") (pin "2") (pinfunction "2_2") (pintype "passive"))
      (node (ref "X7") (pin "2") (pinfunction "2_2") (pintype "passive"))
    )
    (net (code "89") (name "Net-(X4-Pad3)") (class "Default")
      (node (ref "X4") (pin "3") (pinfunction "3_3") (pintype "passive"))
      (node (ref "X7") (pin "3") (pinfunction "3_3") (pintype "passive"))
    )
    (net (code "90") (name "Net-(X4-Pad6)") (class "Default")
      (node (ref "X4") (pin "6") (pinfunction "6_6") (pintype "passive"))
      (node (ref "X7") (pin "6") (pinfunction "6_6") (pintype "passive"))
    )
    (net (code "91") (name "Net-(X8-ACT+)") (class "Default")
      (node (ref "R7") (pin "2") (pinfunction "2_2") (pintype "passive"))
      (node (ref "X8") (pin "10") (pinfunction "ACT+_10") (pintype "bidirectional"))
    )
    (net (code "92") (name "Net-(X8-CG)") (class "Default")
      (node (ref "R2") (pin "2") (pinfunction "2_2") (pintype "passive"))
      (node (ref "X8") (pin "7") (pinfunction "NC_7") (pintype "bidirectional"))
      (node (ref "X8") (pin "8") (pinfunction "CG_8") (pintype "bidirectional"))
    )
    (net (code "93") (name "Net-(X8-CTR)") (class "Default")
      (node (ref "R1") (pin "2") (pinfunction "2_2") (pintype "passive"))
      (node (ref "X8") (pin "4") (pinfunction "CTT_4") (pintype "bidirectional"))
      (node (ref "X8") (pin "5") (pinfunction "CTR_5") (pintype "bidirectional"))
    )
    (net (code "94") (name "Net-(X8-LINK+)") (class "Default")
      (node (ref "R8") (pin "2") (pinfunction "2_2") (pintype "passive"))
      (node (ref "X8") (pin "12") (pinfunction "LINK+_12") (pintype "bidirectional"))
    )
    (net (code "95") (name "Net-(X8-RD-)") (class "Default")
      (node (ref "X5") (pin "6") (pinfunction "6_6") (pintype "passive"))
      (node (ref "X8") (pin "6") (pinfunction "RD-_6") (pintype "bidirectional"))
    )
    (net (code "96") (name "Net-(X8-RX+)") (class "Default")
      (node (ref "X5") (pin "3") (pinfunction "3_3") (pintype "passive"))
      (node (ref "X8") (pin "3") (pinfunction "RX+_3") (pintype "bidirectional"))
    )
    (net (code "97") (name "Net-(X8-TX+)") (class "Default")
      (node (ref "X5") (pin "1") (pinfunction "1_1") (pintype "passive"))
      (node (ref "X8") (pin "1") (pinfunction "TX+_1") (pintype "bidirectional"))
    )
    (net (code "98") (name "Net-(X8-TX-)") (class "Default")
      (node (ref "X5") (pin "2") (pinfunction "2_2") (pintype "passive"))
      (node (ref "X8") (pin "2") (pinfunction "TX-_2") (pintype "bidirectional"))
    )
    (net (code "99") (name "Net-(X10-Pad1)") (class "Default")
      (node (ref "X10") (pin "1") (pinfunction "1_1") (pintype "passive"))
      (node (ref "X12") (pin "1") (pinfunction "1_1") (pintype "passive"))
    )
    (net (code "100") (name "Net-(X10-Pad2)") (class "Default")
      (node (ref "X10") (pin "2") (pinfunction "2_2") (pintype "passive"))
      (node (ref "X12") (pin "2") (pinfunction "2_2") (pintype "passive"))
    )
    (net (code "101") (name "Net-(X10-Pad3)") (class "Default")
      (node (ref "X10") (pin "3") (pinfunction "3_3") (pintype "passive"))
      (node (ref "X12") (pin "3") (pinfunction "3_3") (pintype "passive"))
    )
    (net (code "102") (name "Net-(X10-Pad6)") (class "Default")
      (node (ref "X10") (pin "6") (pinfunction "6_6") (pintype "passive"))
      (node (ref "X12") (pin "6") (pinfunction "6_6") (pintype "passive"))
    )
    (net (code "103") (name "Net-(X11-Pad1)") (class "Default")
      (node (ref "X11") (pin "1") (pinfunction "1_1") (pintype "passive"))
      (node (ref "X9") (pin "1") (pinfunction "1_1") (pintype "passive"))
    )
    (net (code "104") (name "Net-(X11-Pad2)") (class "Default")
      (node (ref "X11") (pin "2") (pinfunction "2_2") (pintype "passive"))
      (node (ref "X9") (pin "2") (pinfunction "2_2") (pintype "passive"))
    )
    (net (code "105") (name "Net-(X11-Pad3)") (class "Default")
      (node (ref "X11") (pin "3") (pinfunction "3_3") (pintype "passive"))
      (node (ref "X9") (pin "3") (pinfunction "3_3") (pintype "passive"))
    )
    (net (code "106") (name "Net-(X11-Pad6)") (class "Default")
      (node (ref "X11") (pin "6") (pinfunction "6_6") (pintype "passive"))
      (node (ref "X9") (pin "6") (pinfunction "6_6") (pintype "passive"))
    )
    (net (code "107") (name "Net-(X14-Pad1)") (class "Default")
      (node (ref "X14") (pin "1") (pinfunction "1_1") (pintype "passive"))
      (node (ref "X16") (pin "1") (pinfunction "1_1") (pintype "passive"))
    )
    (net (code "108") (name "Net-(X14-Pad2)") (class "Default")
      (node (ref "X14") (pin "2") (pinfunction "2_2") (pintype "passive"))
      (node (ref "X16") (pin "2") (pinfunction "2_2") (pintype "passive"))
    )
    (net (code "109") (name "Net-(X14-Pad3)") (class "Default")
      (node (ref "X14") (pin "3") (pinfunction "3_3") (pintype "passive"))
      (node (ref "X16") (pin "3") (pinfunction "3_3") (pintype "passive"))
    )
    (net (code "110") (name "Net-(X14-Pad6)") (class "Default")
      (node (ref "X14") (pin "6") (pinfunction "6_6") (pintype "passive"))
      (node (ref "X16") (pin "6") (pinfunction "6_6") (pintype "passive"))
    )
    (net (code "111") (name "Net-(X15-Pad1)") (class "Default")
      (node (ref "X15") (pin "1") (pinfunction "1_1") (pintype "passive"))
      (node (ref "X17") (pin "1") (pinfunction "1_1") (pintype "passive"))
    )
    (net (code "112") (name "Net-(X15-Pad2)") (class "Default")
      (node (ref "X15") (pin "2") (pinfunction "2_2") (pintype "passive"))
      (node (ref "X17") (pin "2") (pinfunction "2_2") (pintype "passive"))
    )
    (net (code "113") (name "Net-(X15-Pad3)") (class "Default")
      (node (ref "X15") (pin "3") (pinfunction "3_3") (pintype "passive"))
      (node (ref "X17") (pin "3") (pinfunction "3_3") (pintype "passive"))
    )
    (net (code "114") (name "Net-(X15-Pad6)") (class "Default")
      (node (ref "X15") (pin "6") (pinfunction "6_6") (pintype "passive"))
      (node (ref "X17") (pin "6") (pinfunction "6_6") (pintype "passive"))
    )
    (net (code "115") (name "Net-(X19-Pad1)") (class "Default")
      (node (ref "X19") (pin "1") (pinfunction "1_1") (pintype "passive"))
      (node (ref "X23") (pin "1") (pinfunction "1_1") (pintype "passive"))
    )
    (net (code "116") (name "Net-(X19-Pad2)") (class "Default")
      (node (ref "X19") (pin "2") (pinfunction "2_2") (pintype "passive"))
      (node (ref "X23") (pin "2") (pinfunction "2_2") (pintype "passive"))
    )
    (net (code "117") (name "Net-(X19-Pad3)") (class "Default")
      (node (ref "X19") (pin "3") (pinfunction "3_3") (pintype "passive"))
      (node (ref "X23") (pin "3") (pinfunction "3_3") (pintype "passive"))
    )
    (net (code "118") (name "Net-(X19-Pad6)") (class "Default")
      (node (ref "X19") (pin "6") (pinfunction "6_6") (pintype "passive"))
      (node (ref "X23") (pin "6") (pinfunction "6_6") (pintype "passive"))
    )
    (net (code "119") (name "Net-(X24-ACT+)") (class "Default")
      (node (ref "R33") (pin "2") (pinfunction "2_2") (pintype "passive"))
      (node (ref "X24") (pin "10") (pinfunction "ACT+_10") (pintype "bidirectional"))
    )
    (net (code "120") (name "Net-(X24-CG)") (class "Default")
      (node (ref "R30") (pin "2") (pinfunction "2_2") (pintype "passive"))
      (node (ref "X24") (pin "7") (pinfunction "NC_7") (pintype "bidirectional"))
      (node (ref "X24") (pin "8") (pinfunction "CG_8") (pintype "bidirectional"))
    )
    (net (code "121") (name "Net-(X24-CTR)") (class "Default")
      (node (ref "R29") (pin "2") (pinfunction "2_2") (pintype "passive"))
      (node (ref "X24") (pin "4") (pinfunction "CTT_4") (pintype "bidirectional"))
      (node (ref "X24") (pin "5") (pinfunction "CTR_5") (pintype "bidirectional"))
    )
    (net (code "122") (name "Net-(X24-RD-)") (class "Default")
      (node (ref "X20") (pin "6") (pinfunction "6_6") (pintype "passive"))
      (node (ref "X24") (pin "6") (pinfunction "RD-_6") (pintype "bidirectional"))
    )
    (net (code "123") (name "Net-(X24-RX+)") (class "Default")
      (node (ref "X20") (pin "3") (pinfunction "3_3") (pintype "passive"))
      (node (ref "X24") (pin "3") (pinfunction "RX+_3") (pintype "bidirectional"))
    )
    (net (code "124") (name "Net-(X24-TX+)") (class "Default")
      (node (ref "X20") (pin "1") (pinfunction "1_1") (pintype "passive"))
      (node (ref "X24") (pin "1") (pinfunction "TX+_1") (pintype "bidirectional"))
    )
    (net (code "125") (name "Net-(X24-TX-)") (class "Default")
      (node (ref "X20") (pin "2") (pinfunction "2_2") (pintype "passive"))
      (node (ref "X24") (pin "2") (pinfunction "TX-_2") (pintype "bidirectional"))
    )
    (net (code "126") (name "eGND") (class "Default")
      (node (ref "C1") (pin "1") (pinfunction "1_1") (pintype "passive"))
      (node (ref "C10") (pin "1") (pinfunction "1_1") (pintype "passive"))
      (node (ref "C11") (pin "1") (pinfunction "1_1") (pintype "passive"))
      (node (ref "C12") (pin "1") (pinfunction "1_1") (pintype "passive"))
      (node (ref "C13") (pin "1") (pinfunction "1_1") (pintype "passive"))
      (node (ref "C14") (pin "1") (pinfunction "1_1") (pintype "passive"))
      (node (ref "C15") (pin "1") (pinfunction "1_1") (pintype "passive"))
      (node (ref "C16") (pin "1") (pinfunction "1_1") (pintype "passive"))
      (node (ref "C17") (pin "1") (pinfunction "1_1") (pintype "passive"))
      (node (ref "C18") (pin "1") (pinfunction "1_1") (pintype "passive"))
      (node (ref "C2") (pin "1") (pinfunction "1_1") (pintype "passive"))
      (node (ref "C3") (pin "1") (pinfunction "1_1") (pintype "passive"))
      (node (ref "C4") (pin "1") (pinfunction "1_1") (pintype "passive"))
      (node (ref "C5") (pin "1") (pinfunction "1_1") (pintype "passive"))
      (node (ref "C6") (pin "1") (pinfunction "1_1") (pintype "passive"))
      (node (ref "C7") (pin "1") (pinfunction "1_1") (pintype "passive"))
      (node (ref "C8") (pin "1") (pinfunction "1_1") (pintype "passive"))
      (node (ref "C9") (pin "1") (pinfunction "1_1") (pintype "passive"))
      (node (ref "X24") (pin "9") (pinfunction "SHIELD_9") (pintype "bidirectional"))
      (node (ref "X8") (pin "9") (pinfunction "SHIELD_9") (pintype "bidirectional"))
    )
  )
)
